# design.net
KiCad netlist of a schematic drawn in Altium Designer
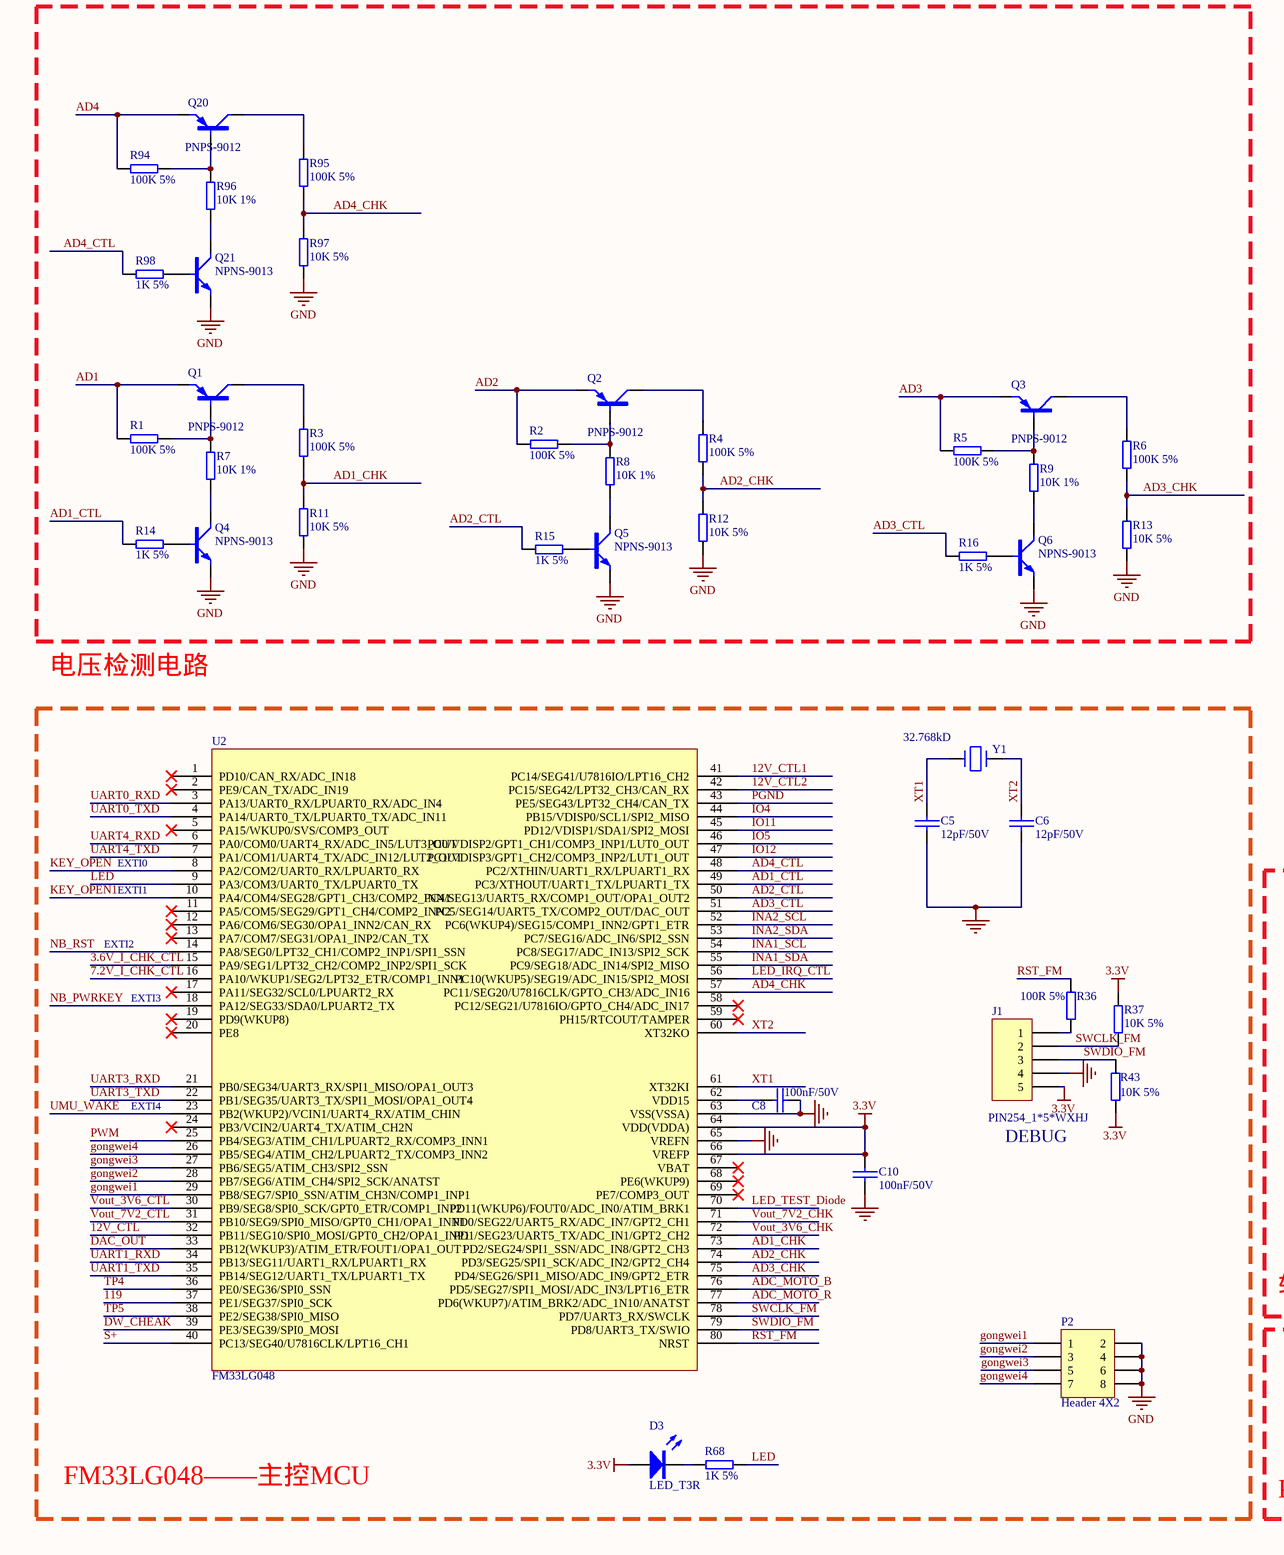
[diagram p0: 主控.SchDoc, left]
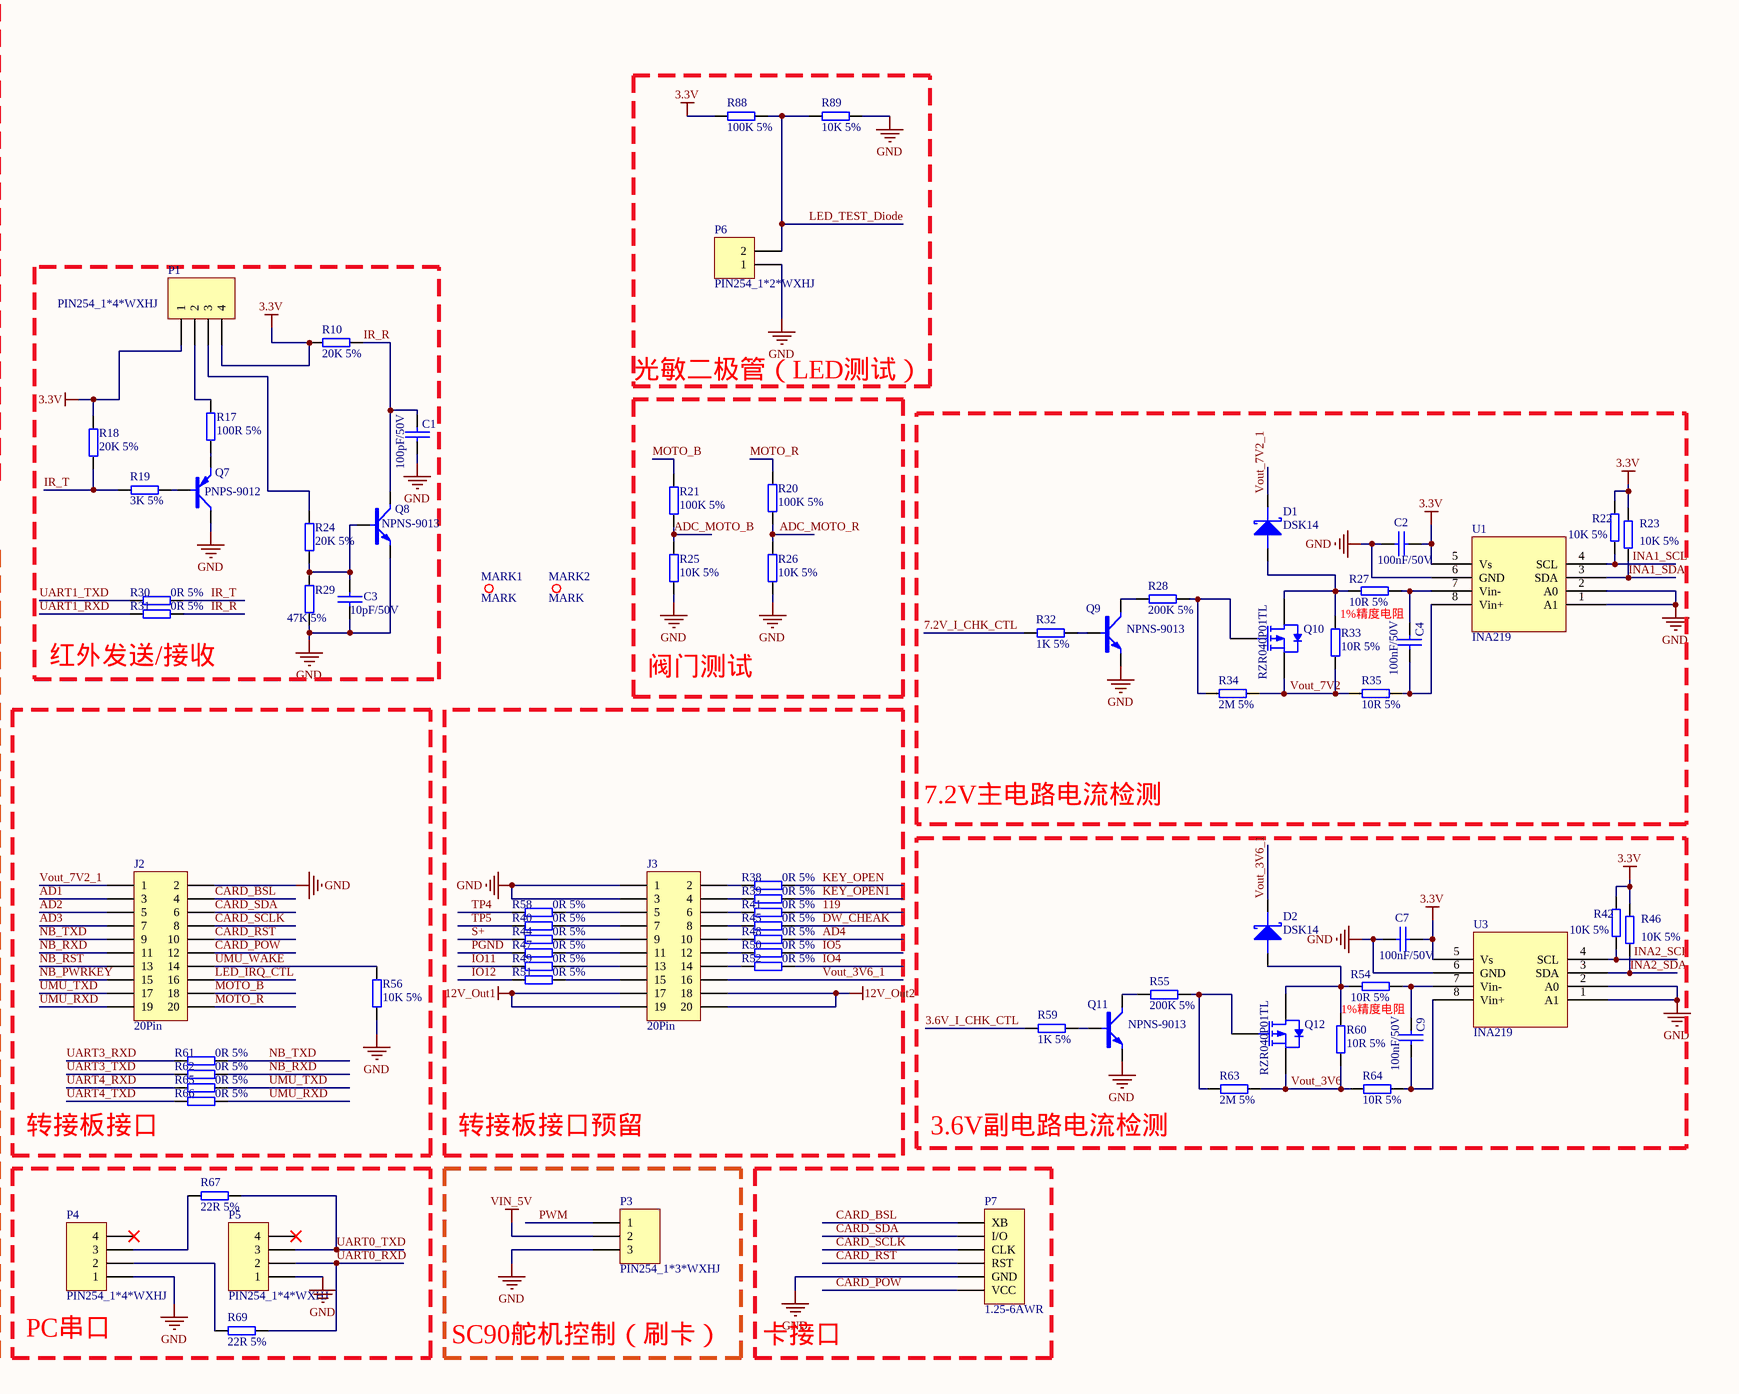
[diagram p1: 主控.SchDoc, right]

(export (version "E")
  (design (tool "Eeschema 10.0.6"))
  (components
    (comp (ref "C1")
      (value "100pF/50V")
      (footprint "CAP0603")
      (description "101pf,50 V,±5%,0603,国巨,CC0603JRNP09BN101")
      (fields (field (name "PART NUMBER") "101020103-0010"))
      (libsource (lib "Database_Libs2") (part "CC03JPO9_101P"))
    )
    (comp (ref "C2")
      (value "100nF/50V")
      (footprint "CAP0603")
      (description "104pF,50 V,±10%,0603,国巨,CC0603KRX7R9BB104")
      (fields (field (name "PART NUMBER") "101020103-0021"))
      (libsource (lib "Database_Libs2") (part "CC03K7R9_100N"))
    )
    (comp (ref "C3")
      (value "10pF/50V")
      (footprint "CAP0603")
      (description "10pF,50 V,±5%,0603,X7R,国巨,CC0603JRNPO9BN100")
      (fields (field (name "PART NUMBER") "101020103-0014"))
      (libsource (lib "Database_Libs2") (part "CC03JPO9_10P"))
    )
    (comp (ref "C4")
      (value "100nF/50V")
      (footprint "CAP0603")
      (description "104pF,50 V,±10%,0603,国巨,CC0603KRX7R9BB104")
      (fields (field (name "PART NUMBER") "101020103-0021"))
      (libsource (lib "Database_Libs2") (part "CC03K7R9_100N"))
    )
    (comp (ref "C5")
      (value "12pF/50V")
      (footprint "CAP0603")
      (description "12P,50 V,±5%,0603,国巨,CC0603JRNPO9BN12")
      (fields (field (name "PART NUMBER") "101020103-0005"))
      (libsource (lib "Database_Libs2") (part "CC03JPO9_12P"))
    )
    (comp (ref "C6")
      (value "12pF/50V")
      (footprint "CAP0603")
      (description "12P,50 V,±5%,0603,国巨,CC0603JRNPO9BN12")
      (fields (field (name "PART NUMBER") "101020103-0005"))
      (libsource (lib "Database_Libs2") (part "CC03JPO9_12P"))
    )
    (comp (ref "C7")
      (value "100nF/50V")
      (footprint "CAP0603")
      (description "104pF,50 V,±10%,0603,国巨,CC0603KRX7R9BB104")
      (fields (field (name "PART NUMBER") "101020103-0021"))
      (libsource (lib "Database_Libs2") (part "CC03K7R9_100N"))
    )
    (comp (ref "C8")
      (value "100nF/50V")
      (footprint "CAP0603")
      (description "104pF,50 V,±10%,0603,国巨,CC0603KRX7R9BB104")
      (fields (field (name "PART NUMBER") "101020103-0021"))
      (libsource (lib "Database_Libs2") (part "CC03K7R9_100N"))
    )
    (comp (ref "C9")
      (value "100nF/50V")
      (footprint "CAP0603")
      (description "104pF,50 V,±10%,0603,国巨,CC0603KRX7R9BB104")
      (fields (field (name "PART NUMBER") "101020103-0021"))
      (libsource (lib "Database_Libs2") (part "CC03K7R9_100N"))
    )
    (comp (ref "C10")
      (value "100nF/50V")
      (footprint "CAP0603")
      (description "104pF,50 V,±10%,0603,国巨,CC0603KRX7R9BB104")
      (fields (field (name "PART NUMBER") "101020103-0021"))
      (libsource (lib "Database_Libs2") (part "CC03K7R9_100N"))
    )
    (comp (ref "D1")
      (value "DSK14")
      (footprint "SOD-123FL")
      (description "DSK14,SOD-123FL,1 A,40 V,28 V,台湾强茂集团苏州群鑫电子,DSK14")
      (fields (field (name "PART NUMBER") "101040101-0043"))
      (libsource (lib "Database_Libs2") (part "02_DSK14"))
    )
    (comp (ref "D2")
      (value "DSK14")
      (footprint "SOD-123FL")
      (description "DSK14,SOD-123FL,1 A,40 V,28 V,台湾强茂集团苏州群鑫电子,DSK14")
      (fields (field (name "PART NUMBER") "101040101-0043"))
      (libsource (lib "Database_Libs2") (part "02_DSK14"))
    )
    (comp (ref "D3")
      (value "LED_T3R")
      (footprint "LED2_300")
      (description "圆形插件,3mm 圆形,插件,红光,湖北匡通电子有限公司,3BB4HC")
      (fields (field (name "PART NUMBER") "101040102-0001"))
      (libsource (lib "Database_Libs2") (part "01-LED_T3R"))
    )
    (comp (ref "J1")
      (value "PIN254_1*5*WXHJ")
      (footprint "PIN254_1*5*1100S")
      (description "1*5 ，Φ1.0 ，2.54mm，直脚,无需焊接器件")
      (fields (field (name "PART NUMBER") "AD_WXHJ_PinHeader_02"))
      (libsource (lib "Database_Libs2") (part "PIN254_1*5*1100S"))
    )
    (comp (ref "J2")
      (value "20Pin")
      (footprint "DC254_2*10 - duplicate")
      (description "DC2 2.54mm 2x10pin,2.54mm间距，2x10pin，32×8.55×27.5mm,母头,双排,双排牛角座")
      (fields (field (name "PART NUMBER") "1010902-0139"))
      (libsource (lib "转接板封装") (part "20Pin"))
    )
    (comp (ref "J3")
      (value "20Pin")
      (footprint "DC254_2*10 - duplicate")
      (description "DC2 2.54mm 2x10pin,2.54mm间距，2x10pin，32×8.55×27.5mm,母头,双排,双排牛角座")
      (fields (field (name "PART NUMBER") "1010902-0139"))
      (libsource (lib "转接板封装") (part "20Pin"))
    )
    (comp (ref "MARK1")
      (value "MARK")
      (footprint "MARK")
      (description "MARK点")
      (fields (field (name "PART NUMBER") "AD_WXHJ_MARK_01"))
      (libsource (lib "转接板封装") (part "MARK"))
    )
    (comp (ref "MARK2")
      (value "MARK")
      (footprint "MARK")
      (description "MARK点")
      (fields (field (name "PART NUMBER") "AD_WXHJ_MARK_01"))
      (libsource (lib "转接板封装") (part "MARK"))
    )
    (comp (ref "P1")
      (value "PIN254_1*4*WXHJ")
      (footprint "PIN254_1*4*1100S")
      (description "1*4 ，Φ1.0 ，2.54mm，直脚,无需焊接器件")
      (fields (field (name "PART NUMBER") "AD_WXHJ_PinHeader_01"))
      (libsource (lib "Database_Libs2") (part "PIN254_1*4*1100S"))
    )
    (comp (ref "P2")
      (value "Header 4X2")
      (footprint "HDR2X4")
      (description "Header, 4-Pin, Dual row")
      (libsource (lib "CBB_Lib_SCH") (part "Header 4X2"))
    )
    (comp (ref "P3")
      (value "PIN254_1*3*WXHJ")
      (footprint "PIN254_1*3*1100S")
      (description "1*3 ，Φ1.0 ，2.54mm，直脚,无需焊接器件")
      (fields (field (name "PART NUMBER") "AD_WXHJ_PinHeader_01"))
      (libsource (lib "模拟计量") (part "PIN254_1*3*1100S"))
    )
    (comp (ref "P4")
      (value "PIN254_1*4*WXHJ")
      (footprint "PIN254_1*4*1100S")
      (description "1*4 ，Φ1.0 ，2.54mm，直脚,无需焊接器件")
      (fields (field (name "PART NUMBER") "AD_WXHJ_PinHeader_01"))
      (libsource (lib "") (part "PIN254_1*4*1100S_1"))
    )
    (comp (ref "P5")
      (value "PIN254_1*4*WXHJ")
      (footprint "PIN254_1*4*1100S")
      (description "1*4 ，Φ1.0 ，2.54mm，直脚,无需焊接器件")
      (fields (field (name "PART NUMBER") "AD_WXHJ_PinHeader_01"))
      (libsource (lib "") (part "PIN254_1*4*1100S_1"))
    )
    (comp (ref "P6")
      (value "PIN254_1*2*WXHJ")
      (footprint "PIN254_1*2*1100S")
      (description "1*2 ，Φ1.0 ，2.54mm，直脚,无需焊接器件")
      (fields (field (name "PART NUMBER") "AD_WXHJ_PinHeader_01"))
      (libsource (lib "转接板封装") (part "PIN254_1*2*1100S"))
    )
    (comp (ref "P7")
      (value "1.25-6AWR")
      (footprint "SMT-1.25-6")
      (description "1.25-6AWR 卷,6针1.25mm,母头,单排,贴片卧式")
      (fields (field (name "PART NUMBER") "1010902-0121"))
      (libsource (lib "Database_Libs2") (part "CARD1608"))
    )
    (comp (ref "Q1")
      (value "PNPS-9012")
      (footprint "SOT-23")
      (description "9012,PNP,SOT-23,JCET;长电,S9012")
      (fields (field (name "PART NUMBER") "101040201-0001"))
      (libsource (lib "Database_Libs2") (part "03_PNPS-9012"))
    )
    (comp (ref "Q2")
      (value "PNPS-9012")
      (footprint "SOT-23")
      (description "9012,PNP,SOT-23,JCET;长电,S9012")
      (fields (field (name "PART NUMBER") "101040201-0001"))
      (libsource (lib "Database_Libs2") (part "03_PNPS-9012"))
    )
    (comp (ref "Q3")
      (value "PNPS-9012")
      (footprint "SOT-23")
      (description "9012,PNP,SOT-23,JCET;长电,S9012")
      (fields (field (name "PART NUMBER") "101040201-0001"))
      (libsource (lib "Database_Libs2") (part "03_PNPS-9012"))
    )
    (comp (ref "Q4")
      (value "NPNS-9013")
      (footprint "SOT-23")
      (description "9013,NPN,SOT-23,长电,S9013")
      (fields (field (name "PART NUMBER") "101040201-0002"))
      (libsource (lib "Database_Libs2") (part "03_NPNS-9013"))
    )
    (comp (ref "Q5")
      (value "NPNS-9013")
      (footprint "SOT-23")
      (description "9013,NPN,SOT-23,长电,S9013")
      (fields (field (name "PART NUMBER") "101040201-0002"))
      (libsource (lib "Database_Libs2") (part "03_NPNS-9013"))
    )
    (comp (ref "Q6")
      (value "NPNS-9013")
      (footprint "SOT-23")
      (description "9013,NPN,SOT-23,长电,S9013")
      (fields (field (name "PART NUMBER") "101040201-0002"))
      (libsource (lib "Database_Libs2") (part "03_NPNS-9013"))
    )
    (comp (ref "Q7")
      (value "PNPS-9012")
      (footprint "SOT-23")
      (description "9012,PNP,SOT-23,JCET;长电,S9012")
      (fields (field (name "PART NUMBER") "101040201-0001"))
      (libsource (lib "Database_Libs2") (part "03_PNPS-9012"))
    )
    (comp (ref "Q8")
      (value "NPNS-9013")
      (footprint "SOT-23")
      (description "9013,NPN,SOT-23,长电,S9013")
      (fields (field (name "PART NUMBER") "101040201-0002"))
      (libsource (lib "Database_Libs2") (part "03_NPNS-9013"))
    )
    (comp (ref "Q9")
      (value "NPNS-9013")
      (footprint "SOT-23")
      (description "9013,NPN,SOT-23,长电,S9013")
      (fields (field (name "PART NUMBER") "101040201-0002"))
      (libsource (lib "Database_Libs2") (part "03_NPNS-9013"))
    )
    (comp (ref "Q10")
      (value "RZR040P01TL")
      (footprint "SOT-23")
      (description "RZR040P01TL；1.5v导通,P-MOS,SOT-23,罗姆,RZR040P01TL")
      (fields (field (name "PART NUMBER") "101040201-0010"))
      (libsource (lib "Database_Libs2") (part "03_P-RZR040P01TL"))
    )
    (comp (ref "Q11")
      (value "NPNS-9013")
      (footprint "SOT-23")
      (description "9013,NPN,SOT-23,长电,S9013")
      (fields (field (name "PART NUMBER") "101040201-0002"))
      (libsource (lib "Database_Libs2") (part "03_NPNS-9013"))
    )
    (comp (ref "Q12")
      (value "RZR040P01TL")
      (footprint "SOT-23")
      (description "RZR040P01TL；1.5v导通,P-MOS,SOT-23,罗姆,RZR040P01TL")
      (fields (field (name "PART NUMBER") "101040201-0010"))
      (libsource (lib "Database_Libs2") (part "03_P-RZR040P01TL"))
    )
    (comp (ref "Q20")
      (value "PNPS-9012")
      (footprint "SOT-23")
      (description "9012,PNP,SOT-23,JCET;长电,S9012")
      (fields (field (name "PART NUMBER") "101040201-0001"))
      (libsource (lib "Database_Libs2") (part "03_PNPS-9012"))
    )
    (comp (ref "Q21")
      (value "NPNS-9013")
      (footprint "SOT-23")
      (description "9013,NPN,SOT-23,长电,S9013")
      (fields (field (name "PART NUMBER") "101040201-0002"))
      (libsource (lib "Database_Libs2") (part "03_NPNS-9013"))
    )
    (comp (ref "R1")
      (value "100K 5%")
      (footprint "RES0603")
      (description "国巨,±5%,0603,,155 ℃,-55 ℃,RC0603JR-07100KL,无铅,100 ppm/℃,1/10W,,100K")
      (fields (field (name "PART NUMBER") "101010103-0005"))
      (libsource (lib "Database_Libs2") (part "RC03J_100K"))
    )
    (comp (ref "R2")
      (value "100K 5%")
      (footprint "RES0603")
      (description "国巨,±5%,0603,,155 ℃,-55 ℃,RC0603JR-07100KL,无铅,100 ppm/℃,1/10W,,100K")
      (fields (field (name "PART NUMBER") "101010103-0005"))
      (libsource (lib "Database_Libs2") (part "RC03J_100K"))
    )
    (comp (ref "R3")
      (value "100K 5%")
      (footprint "RES0603")
      (description "国巨,±5%,0603,,155 ℃,-55 ℃,RC0603JR-07100KL,无铅,100 ppm/℃,1/10W,,100K")
      (fields (field (name "PART NUMBER") "101010103-0005"))
      (libsource (lib "Database_Libs2") (part "RC03J_100K"))
    )
    (comp (ref "R4")
      (value "100K 5%")
      (footprint "RES0603")
      (description "国巨,±5%,0603,,155 ℃,-55 ℃,RC0603JR-07100KL,无铅,100 ppm/℃,1/10W,,100K")
      (fields (field (name "PART NUMBER") "101010103-0005"))
      (libsource (lib "Database_Libs2") (part "RC03J_100K"))
    )
    (comp (ref "R5")
      (value "100K 5%")
      (footprint "RES0603")
      (description "国巨,±5%,0603,,155 ℃,-55 ℃,RC0603JR-07100KL,无铅,100 ppm/℃,1/10W,,100K")
      (fields (field (name "PART NUMBER") "101010103-0005"))
      (libsource (lib "Database_Libs2") (part "RC03J_100K"))
    )
    (comp (ref "R6")
      (value "100K 5%")
      (footprint "RES0603")
      (description "国巨,±5%,0603,,155 ℃,-55 ℃,RC0603JR-07100KL,无铅,100 ppm/℃,1/10W,,100K")
      (fields (field (name "PART NUMBER") "101010103-0005"))
      (libsource (lib "Database_Libs2") (part "RC03J_100K"))
    )
    (comp (ref "R7")
      (value "10K 1%")
      (footprint "RES0603")
      (description "10K±1%,1/10W,0603")
      (fields (field (name "PART NUMBER") "101010103-0052"))
      (libsource (lib "Database_Libs2") (part "RC03J_10K"))
    )
    (comp (ref "R8")
      (value "10K 1%")
      (footprint "RES0603")
      (description "10K±1%,1/10W,0603")
      (fields (field (name "PART NUMBER") "101010103-0052"))
      (libsource (lib "Database_Libs2") (part "RC03J_10K"))
    )
    (comp (ref "R9")
      (value "10K 1%")
      (footprint "RES0603")
      (description "10K±1%,1/10W,0603")
      (fields (field (name "PART NUMBER") "101010103-0052"))
      (libsource (lib "Database_Libs2") (part "RC03J_10K"))
    )
    (comp (ref "R10")
      (value "20K 5%")
      (footprint "RES0603")
      (description "国巨,±5%,0603,,155 ℃,-55 ℃,RC0603JR-0720KL,无铅,200 ppm/℃,1/10W,,20K")
      (fields (field (name "PART NUMBER") "101010103-0004"))
      (libsource (lib "Database_Libs2") (part "RC03J_20K"))
    )
    (comp (ref "R11")
      (value "10K 5%")
      (footprint "RES0603")
      (description "国巨,±5%,0603,,155 ℃,-55 ℃,RC0603JR-0710KL,无铅,200 ppm/℃,1/10W,,10K")
      (fields (field (name "PART NUMBER") "101010103-0003"))
      (libsource (lib "Database_Libs2") (part "RC03J_10K"))
    )
    (comp (ref "R12")
      (value "10K 5%")
      (footprint "RES0603")
      (description "国巨,±5%,0603,,155 ℃,-55 ℃,RC0603JR-0710KL,无铅,200 ppm/℃,1/10W,,10K")
      (fields (field (name "PART NUMBER") "101010103-0003"))
      (libsource (lib "Database_Libs2") (part "RC03J_10K"))
    )
    (comp (ref "R13")
      (value "10K 5%")
      (footprint "RES0603")
      (description "国巨,±5%,0603,,155 ℃,-55 ℃,RC0603JR-0710KL,无铅,200 ppm/℃,1/10W,,10K")
      (fields (field (name "PART NUMBER") "101010103-0003"))
      (libsource (lib "Database_Libs2") (part "RC03J_10K"))
    )
    (comp (ref "R14")
      (value "1K 5%")
      (footprint "RES0603")
      (description "1K,±5%,1/10W,0603,国巨,RC0603JR-071KL")
      (fields (field (name "PART NUMBER") "101010103-0008"))
      (libsource (lib "Database_Libs2") (part "RC03J_1K"))
    )
    (comp (ref "R15")
      (value "1K 5%")
      (footprint "RES0603")
      (description "1K,±5%,1/10W,0603,国巨,RC0603JR-071KL")
      (fields (field (name "PART NUMBER") "101010103-0008"))
      (libsource (lib "Database_Libs2") (part "RC03J_1K"))
    )
    (comp (ref "R16")
      (value "1K 5%")
      (footprint "RES0603")
      (description "1K,±5%,1/10W,0603,国巨,RC0603JR-071KL")
      (fields (field (name "PART NUMBER") "101010103-0008"))
      (libsource (lib "Database_Libs2") (part "RC03J_1K"))
    )
    (comp (ref "R17")
      (value "100R 5%")
      (footprint "RES0603")
      (description "100R,±5%,1/10W,0603,国巨,RC0603JR-07100RL")
      (fields (field (name "PART NUMBER") "101010103-0022"))
      (libsource (lib "Database_Libs2") (part "RC03J_100R"))
    )
    (comp (ref "R18")
      (value "20K 5%")
      (footprint "RES0603")
      (description "国巨,±5%,0603,,155 ℃,-55 ℃,RC0603JR-0720KL,无铅,200 ppm/℃,1/10W,,20K")
      (fields (field (name "PART NUMBER") "101010103-0004"))
      (libsource (lib "Database_Libs2") (part "RC03J_20K"))
    )
    (comp (ref "R19")
      (value "3K 5%")
      (footprint "RES0603")
      (description "国巨,±5%,0603,,155 ℃,-55 ℃,RC0603JR-073KL,无铅,100 ppm/℃,1/10W,,3K")
      (fields (field (name "PART NUMBER") "101010103-0006"))
      (libsource (lib "Database_Libs2") (part "RC03J_3K"))
    )
    (comp (ref "R20")
      (value "100K 5%")
      (footprint "RES0603")
      (description "100K±5%,1/10W,0603")
      (fields (field (name "PART NUMBER") "101010103-0005"))
      (libsource (lib "Database_Libs1") (part "RC03JF_100K"))
    )
    (comp (ref "R21")
      (value "100K 5%")
      (footprint "RES0603")
      (description "100K±5%,1/10W,0603")
      (fields (field (name "PART NUMBER") "101010103-0005"))
      (libsource (lib "Database_Libs1") (part "RC03JF_100K"))
    )
    (comp (ref "R22")
      (value "10K 5%")
      (footprint "RES0603")
      (description "国巨,±5%,0603,,155 ℃,-55 ℃,RC0603JR-0710KL,无铅,200 ppm/℃,1/10W,,10K")
      (fields (field (name "PART NUMBER") "101010103-0003"))
      (libsource (lib "Database_Libs2") (part "RC03J_10K"))
    )
    (comp (ref "R23")
      (value "10K 5%")
      (footprint "RES0603")
      (description "国巨,±5%,0603,,155 ℃,-55 ℃,RC0603JR-0710KL,无铅,200 ppm/℃,1/10W,,10K")
      (fields (field (name "PART NUMBER") "101010103-0003"))
      (libsource (lib "Database_Libs2") (part "RC03J_10K"))
    )
    (comp (ref "R24")
      (value "20K 5%")
      (footprint "RES0603")
      (description "国巨,±5%,0603,,155 ℃,-55 ℃,RC0603JR-0720KL,无铅,200 ppm/℃,1/10W,,20K")
      (fields (field (name "PART NUMBER") "101010103-0004"))
      (libsource (lib "Database_Libs2") (part "RC03J_20K"))
    )
    (comp (ref "R25")
      (value "10K 5%")
      (footprint "RES0603")
      (description "国巨,±5%,0603,,155 ℃,-55 ℃,RC0603JR-0710KL,无铅,200 ppm/℃,1/10W,,10K")
      (fields (field (name "PART NUMBER") "101010103-0003"))
      (libsource (lib "Database_Libs2") (part "RC03J_10K"))
    )
    (comp (ref "R26")
      (value "10K 5%")
      (footprint "RES0603")
      (description "国巨,±5%,0603,,155 ℃,-55 ℃,RC0603JR-0710KL,无铅,200 ppm/℃,1/10W,,10K")
      (fields (field (name "PART NUMBER") "101010103-0003"))
      (libsource (lib "Database_Libs2") (part "RC03J_10K"))
    )
    (comp (ref "R27")
      (value "10R 5%")
      (footprint "RES0603")
      (description "10R,±5%,1/10W,0603,国巨,RC0603JR-0710RL")
      (fields (field (name "PART NUMBER") "101010103-0017"))
      (libsource (lib "Database_Libs2") (part "RC03J_10R"))
    )
    (comp (ref "R28")
      (value "200K 5%")
      (footprint "RES0603")
      (description "200K,±5%,1/10W,0603,国巨,RC0603JR-07200KL")
      (fields (field (name "PART NUMBER") "101010103-0034"))
      (libsource (lib "Database_Libs2") (part "RC03J_200K"))
    )
    (comp (ref "R29")
      (value "47K 5%")
      (footprint "RES0603")
      (description "47K,±5%,1/10W,0603,国巨,RC0603JR-0747KL")
      (fields (field (name "PART NUMBER") "101010103-0012"))
      (libsource (lib "Database_Libs2") (part "RC03J_47K"))
    )
    (comp (ref "R30")
      (value "0R 5%")
      (footprint "RES0603")
      (description "国巨,±5%,0603,,155 ℃,-55 ℃,RC0603J2-070RL,无铅,200 ppm/℃,1/10W,,0R")
      (fields (field (name "PART NUMBER") "101010103-0001"))
      (libsource (lib "Database_Libs2") (part "RC03J_0R"))
    )
    (comp (ref "R31")
      (value "0R 5%")
      (footprint "RES0603")
      (description "国巨,±5%,0603,,155 ℃,-55 ℃,RC0603J2-070RL,无铅,200 ppm/℃,1/10W,,0R")
      (fields (field (name "PART NUMBER") "101010103-0001"))
      (libsource (lib "Database_Libs2") (part "RC03J_0R"))
    )
    (comp (ref "R32")
      (value "1K 5%")
      (footprint "RES0603")
      (description "1K,±5%,1/10W,0603,国巨,RC0603JR-071KL")
      (fields (field (name "PART NUMBER") "101010103-0008"))
      (libsource (lib "Database_Libs2") (part "RC03J_1K"))
    )
    (comp (ref "R33")
      (value "10R 5%")
      (footprint "RES0603")
      (description "10R,±5%,1/10W,0603,国巨,RC0603JR-0710RL")
      (fields (field (name "PART NUMBER") "101010103-0017"))
      (libsource (lib "Database_Libs2") (part "RC03J_10R"))
    )
    (comp (ref "R34")
      (value "2M 5%")
      (footprint "RES0603")
      (description "国巨,±5%,0603,,155 ℃,-55 ℃,RC0603JR-072ML,含铅,100 ppm/℃,1/10W,,2M")
      (fields (field (name "PART NUMBER") "101010103-0025"))
      (libsource (lib "Database_Libs2") (part "RC03J_2M"))
    )
    (comp (ref "R35")
      (value "10R 5%")
      (footprint "RES0603")
      (description "10R,±5%,1/10W,0603,国巨,RC0603JR-0710RL")
      (fields (field (name "PART NUMBER") "101010103-0017"))
      (libsource (lib "Database_Libs2") (part "RC03J_10R"))
    )
    (comp (ref "R36")
      (value "100R 5%")
      (footprint "RES0603")
      (description "100R,±5%,1/10W,0603,国巨,RC0603JR-07100RL")
      (fields (field (name "PART NUMBER") "101010103-0022"))
      (libsource (lib "Database_Libs2") (part "RC03J_100R"))
    )
    (comp (ref "R37")
      (value "10K 5%")
      (footprint "RES0603")
      (description "国巨,±5%,0603,,155 ℃,-55 ℃,RC0603JR-0710KL,无铅,200 ppm/℃,1/10W,,10K")
      (fields (field (name "PART NUMBER") "101010103-0003"))
      (libsource (lib "Database_Libs2") (part "RC03J_10K"))
    )
    (comp (ref "R38")
      (value "0R 5%")
      (footprint "RES0603")
      (description "国巨,±5%,0603,,155 ℃,-55 ℃,RC0603J2-070RL,无铅,200 ppm/℃,1/10W,,0R")
      (fields (field (name "PART NUMBER") "101010103-0001"))
      (libsource (lib "Database_Libs2") (part "RC03J_0R"))
    )
    (comp (ref "R39")
      (value "0R 5%")
      (footprint "RES0603")
      (description "国巨,±5%,0603,,155 ℃,-55 ℃,RC0603J2-070RL,无铅,200 ppm/℃,1/10W,,0R")
      (fields (field (name "PART NUMBER") "101010103-0001"))
      (libsource (lib "Database_Libs2") (part "RC03J_0R"))
    )
    (comp (ref "R40")
      (value "0R 5%")
      (footprint "RES0603")
      (description "国巨,±5%,0603,,155 ℃,-55 ℃,RC0603J2-070RL,无铅,200 ppm/℃,1/10W,,0R")
      (fields (field (name "PART NUMBER") "101010103-0001"))
      (libsource (lib "Database_Libs2") (part "RC03J_0R"))
    )
    (comp (ref "R41")
      (value "0R 5%")
      (footprint "RES0603")
      (description "国巨,±5%,0603,,155 ℃,-55 ℃,RC0603J2-070RL,无铅,200 ppm/℃,1/10W,,0R")
      (fields (field (name "PART NUMBER") "101010103-0001"))
      (libsource (lib "Database_Libs2") (part "RC03J_0R"))
    )
    (comp (ref "R42")
      (value "10K 5%")
      (footprint "RES0603")
      (description "国巨,±5%,0603,,155 ℃,-55 ℃,RC0603JR-0710KL,无铅,200 ppm/℃,1/10W,,10K")
      (fields (field (name "PART NUMBER") "101010103-0003"))
      (libsource (lib "Database_Libs2") (part "RC03J_10K"))
    )
    (comp (ref "R43")
      (value "10K 5%")
      (footprint "RES0603")
      (description "国巨,±5%,0603,,155 ℃,-55 ℃,RC0603JR-0710KL,无铅,200 ppm/℃,1/10W,,10K")
      (fields (field (name "PART NUMBER") "101010103-0003"))
      (libsource (lib "Database_Libs2") (part "RC03J_10K"))
    )
    (comp (ref "R44")
      (value "0R 5%")
      (footprint "RES0603")
      (description "国巨,±5%,0603,,155 ℃,-55 ℃,RC0603J2-070RL,无铅,200 ppm/℃,1/10W,,0R")
      (fields (field (name "PART NUMBER") "101010103-0001"))
      (libsource (lib "Database_Libs2") (part "RC03J_0R"))
    )
    (comp (ref "R45")
      (value "0R 5%")
      (footprint "RES0603")
      (description "国巨,±5%,0603,,155 ℃,-55 ℃,RC0603J2-070RL,无铅,200 ppm/℃,1/10W,,0R")
      (fields (field (name "PART NUMBER") "101010103-0001"))
      (libsource (lib "Database_Libs2") (part "RC03J_0R"))
    )
    (comp (ref "R46")
      (value "10K 5%")
      (footprint "RES0603")
      (description "国巨,±5%,0603,,155 ℃,-55 ℃,RC0603JR-0710KL,无铅,200 ppm/℃,1/10W,,10K")
      (fields (field (name "PART NUMBER") "101010103-0003"))
      (libsource (lib "Database_Libs2") (part "RC03J_10K"))
    )
    (comp (ref "R47")
      (value "0R 5%")
      (footprint "RES0603")
      (description "国巨,±5%,0603,,155 ℃,-55 ℃,RC0603J2-070RL,无铅,200 ppm/℃,1/10W,,0R")
      (fields (field (name "PART NUMBER") "101010103-0001"))
      (libsource (lib "Database_Libs2") (part "RC03J_0R"))
    )
    (comp (ref "R48")
      (value "0R 5%")
      (footprint "RES0603")
      (description "国巨,±5%,0603,,155 ℃,-55 ℃,RC0603J2-070RL,无铅,200 ppm/℃,1/10W,,0R")
      (fields (field (name "PART NUMBER") "101010103-0001"))
      (libsource (lib "Database_Libs2") (part "RC03J_0R"))
    )
    (comp (ref "R49")
      (value "0R 5%")
      (footprint "RES0603")
      (description "国巨,±5%,0603,,155 ℃,-55 ℃,RC0603J2-070RL,无铅,200 ppm/℃,1/10W,,0R")
      (fields (field (name "PART NUMBER") "101010103-0001"))
      (libsource (lib "Database_Libs2") (part "RC03J_0R"))
    )
    (comp (ref "R50")
      (value "0R 5%")
      (footprint "RES0603")
      (description "国巨,±5%,0603,,155 ℃,-55 ℃,RC0603J2-070RL,无铅,200 ppm/℃,1/10W,,0R")
      (fields (field (name "PART NUMBER") "101010103-0001"))
      (libsource (lib "Database_Libs2") (part "RC03J_0R"))
    )
    (comp (ref "R51")
      (value "0R 5%")
      (footprint "RES0603")
      (description "国巨,±5%,0603,,155 ℃,-55 ℃,RC0603J2-070RL,无铅,200 ppm/℃,1/10W,,0R")
      (fields (field (name "PART NUMBER") "101010103-0001"))
      (libsource (lib "Database_Libs2") (part "RC03J_0R"))
    )
    (comp (ref "R52")
      (value "0R 5%")
      (footprint "RES0603")
      (description "国巨,±5%,0603,,155 ℃,-55 ℃,RC0603J2-070RL,无铅,200 ppm/℃,1/10W,,0R")
      (fields (field (name "PART NUMBER") "101010103-0001"))
      (libsource (lib "Database_Libs2") (part "RC03J_0R"))
    )
    (comp (ref "R54")
      (value "10R 5%")
      (footprint "RES0603")
      (description "10R,±5%,1/10W,0603,国巨,RC0603JR-0710RL")
      (fields (field (name "PART NUMBER") "101010103-0017"))
      (libsource (lib "Database_Libs2") (part "RC03J_10R"))
    )
    (comp (ref "R55")
      (value "200K 5%")
      (footprint "RES0603")
      (description "200K,±5%,1/10W,0603,国巨,RC0603JR-07200KL")
      (fields (field (name "PART NUMBER") "101010103-0034"))
      (libsource (lib "Database_Libs2") (part "RC03J_200K"))
    )
    (comp (ref "R56")
      (value "10K 5%")
      (footprint "RES0603")
      (description "国巨,±5%,0603,,155 ℃,-55 ℃,RC0603JR-0710KL,无铅,200 ppm/℃,1/10W,,10K")
      (fields (field (name "PART NUMBER") "101010103-0003"))
      (libsource (lib "Database_Libs2") (part "RC03J_10K"))
    )
    (comp (ref "R58")
      (value "0R 5%")
      (footprint "RES0603")
      (description "国巨,±5%,0603,,155 ℃,-55 ℃,RC0603J2-070RL,无铅,200 ppm/℃,1/10W,,0R")
      (fields (field (name "PART NUMBER") "101010103-0001"))
      (libsource (lib "Database_Libs2") (part "RC03J_0R"))
    )
    (comp (ref "R59")
      (value "1K 5%")
      (footprint "RES0603")
      (description "1K,±5%,1/10W,0603,国巨,RC0603JR-071KL")
      (fields (field (name "PART NUMBER") "101010103-0008"))
      (libsource (lib "Database_Libs2") (part "RC03J_1K"))
    )
    (comp (ref "R60")
      (value "10R 5%")
      (footprint "RES0603")
      (description "10R,±5%,1/10W,0603,国巨,RC0603JR-0710RL")
      (fields (field (name "PART NUMBER") "101010103-0017"))
      (libsource (lib "Database_Libs2") (part "RC03J_10R"))
    )
    (comp (ref "R61")
      (value "0R 5%")
      (footprint "RES0603")
      (description "国巨,±5%,0603,,155 ℃,-55 ℃,RC0603J2-070RL,无铅,200 ppm/℃,1/10W,,0R")
      (fields (field (name "PART NUMBER") "101010103-0001"))
      (libsource (lib "Database_Libs2") (part "RC03J_0R"))
    )
    (comp (ref "R62")
      (value "0R 5%")
      (footprint "RES0603")
      (description "国巨,±5%,0603,,155 ℃,-55 ℃,RC0603J2-070RL,无铅,200 ppm/℃,1/10W,,0R")
      (fields (field (name "PART NUMBER") "101010103-0001"))
      (libsource (lib "Database_Libs2") (part "RC03J_0R"))
    )
    (comp (ref "R63")
      (value "2M 5%")
      (footprint "RES0603")
      (description "国巨,±5%,0603,,155 ℃,-55 ℃,RC0603JR-072ML,含铅,100 ppm/℃,1/10W,,2M")
      (fields (field (name "PART NUMBER") "101010103-0025"))
      (libsource (lib "Database_Libs2") (part "RC03J_2M"))
    )
    (comp (ref "R64")
      (value "10R 5%")
      (footprint "RES0603")
      (description "10R,±5%,1/10W,0603,国巨,RC0603JR-0710RL")
      (fields (field (name "PART NUMBER") "101010103-0017"))
      (libsource (lib "Database_Libs2") (part "RC03J_10R"))
    )
    (comp (ref "R65")
      (value "0R 5%")
      (footprint "RES0603")
      (description "国巨,±5%,0603,,155 ℃,-55 ℃,RC0603J2-070RL,无铅,200 ppm/℃,1/10W,,0R")
      (fields (field (name "PART NUMBER") "101010103-0001"))
      (libsource (lib "Database_Libs2") (part "RC03J_0R"))
    )
    (comp (ref "R66")
      (value "0R 5%")
      (footprint "RES0603")
      (description "国巨,±5%,0603,,155 ℃,-55 ℃,RC0603J2-070RL,无铅,200 ppm/℃,1/10W,,0R")
      (fields (field (name "PART NUMBER") "101010103-0001"))
      (libsource (lib "Database_Libs2") (part "RC03J_0R"))
    )
    (comp (ref "R67")
      (value "22R 5%")
      (footprint "RES0603")
      (description "国巨,±5%,0603,,155 ℃,-55 ℃,RC0603JR-0722RL,无铅,200 ppm/℃,1/10W,,22欧")
      (fields (field (name "PART NUMBER") "101010103-0009"))
      (libsource (lib "Database_Libs2") (part "RC03J_22R"))
    )
    (comp (ref "R68")
      (value "1K 5%")
      (footprint "RES0603")
      (description "1K,±5%,1/10W,0603,国巨,RC0603JR-071KL")
      (fields (field (name "PART NUMBER") "101010103-0008"))
      (libsource (lib "Database_Libs2") (part "RC03J_1K"))
    )
    (comp (ref "R69")
      (value "22R 5%")
      (footprint "RES0603")
      (description "国巨,±5%,0603,,155 ℃,-55 ℃,RC0603JR-0722RL,无铅,200 ppm/℃,1/10W,,22欧")
      (fields (field (name "PART NUMBER") "101010103-0009"))
      (libsource (lib "Database_Libs2") (part "RC03J_22R"))
    )
    (comp (ref "R88")
      (value "100K 5%")
      (footprint "RES0603")
      (description "国巨,±5%,0603,,155 ℃,-55 ℃,RC0603JR-07100KL,无铅,100 ppm/℃,1/10W,,100K")
      (fields (field (name "PART NUMBER") "101010103-0005"))
      (libsource (lib "Database_Libs2") (part "RC03J_100K"))
    )
    (comp (ref "R89")
      (value "10K 5%")
      (footprint "RES0603")
      (description "国巨,±5%,0603,,155 ℃,-55 ℃,RC0603JR-0710KL,无铅,200 ppm/℃,1/10W,,10K")
      (fields (field (name "PART NUMBER") "101010103-0003"))
      (libsource (lib "转接板封装") (part "RC03J_10K"))
    )
    (comp (ref "R94")
      (value "100K 5%")
      (footprint "RES0603")
      (description "国巨,±5%,0603,,155 ℃,-55 ℃,RC0603JR-07100KL,无铅,100 ppm/℃,1/10W,,100K")
      (fields (field (name "PART NUMBER") "101010103-0005"))
      (libsource (lib "Database_Libs2") (part "RC03J_100K"))
    )
    (comp (ref "R95")
      (value "100K 5%")
      (footprint "RES0603")
      (description "国巨,±5%,0603,,155 ℃,-55 ℃,RC0603JR-07100KL,无铅,100 ppm/℃,1/10W,,100K")
      (fields (field (name "PART NUMBER") "101010103-0005"))
      (libsource (lib "Database_Libs2") (part "RC03J_100K"))
    )
    (comp (ref "R96")
      (value "10K 1%")
      (footprint "RES0603")
      (description "10K±1%,1/10W,0603")
      (fields (field (name "PART NUMBER") "101010103-0052"))
      (libsource (lib "Database_Libs2") (part "RC03J_10K"))
    )
    (comp (ref "R97")
      (value "10K 5%")
      (footprint "RES0603")
      (description "国巨,±5%,0603,,155 ℃,-55 ℃,RC0603JR-0710KL,无铅,200 ppm/℃,1/10W,,10K")
      (fields (field (name "PART NUMBER") "101010103-0003"))
      (libsource (lib "Database_Libs2") (part "RC03J_10K"))
    )
    (comp (ref "R98")
      (value "1K 5%")
      (footprint "RES0603")
      (description "1K,±5%,1/10W,0603,国巨,RC0603JR-071KL")
      (fields (field (name "PART NUMBER") "101010103-0008"))
      (libsource (lib "Database_Libs2") (part "RC03J_1K"))
    )
    (comp (ref "U1") (value "INA219") (footprint "SO-8") (libsource (lib "转接板封装") (part "INA219")))
    (comp (ref "U2")
      (value "FM33LG048")
      (footprint "LQFP80")
      (description "101050101-0261")
      (libsource (lib "转接板封装") (part "FM33LG048"))
    )
    (comp (ref "U3") (value "INA219") (footprint "SO-8") (libsource (lib "转接板封装") (part "INA219")))
    (comp (ref "Y1")
      (value "32.768kD")
      (footprint "SMD-3215_2P")
      (fields (field (name "PART NUMBER") "1010601-0020"))
      (libsource (lib "Database_Libs2") (part "04_XTALSG12MD_32.768kD"))
    )
  )
  (nets
    (net (code "1") (name "/3.6V_I_CHK_CTL") (class "Default")
      (node (ref "R59") (pin "2") (pinfunction "2_2") (pintype "passive"))
      (node (ref "U2") (pin "15") (pinfunction "PA9/SEG1/LPT32_CH2/COMP2_INP2/SPI1_SCK_15") (pintype "passive"))
    )
    (net (code "2") (name "/7.2V_I_CHK_CTL") (class "Default")
      (node (ref "R32") (pin "2") (pinfunction "2_2") (pintype "passive"))
      (node (ref "U2") (pin "16") (pinfunction "PA10/WKUP1/SEG2/LPT32_ETR/COMP1_INN1_16") (pintype "passive"))
    )
    (net (code "3") (name "/12V_CTL") (class "Default")
      (node (ref "U2") (pin "32") (pinfunction "PB11/SEG10/SPI0_MOSI/GPT0_CH2/OPA1_INP1_32") (pintype "passive"))
    )
    (net (code "4") (name "/12V_CTL1") (class "Default")
      (node (ref "U2") (pin "41") (pinfunction "PC14/SEG41/U7816IO/LPT16_CH2_41") (pintype "passive"))
    )
    (net (code "5") (name "/12V_CTL2") (class "Default")
      (node (ref "U2") (pin "42") (pinfunction "PC15/SEG42/LPT32_CH3/CAN_RX_42") (pintype "passive"))
    )
    (net (code "6") (name "/119") (class "Default")
      (node (ref "R41") (pin "2") (pinfunction "2_2") (pintype "passive"))
      (node (ref "U2") (pin "37") (pinfunction "PE1/SEG37/SPI0_SCK_37") (pintype "passive"))
    )
    (net (code "7") (name "/AD1") (class "Default")
      (node (ref "J2") (pin "3") (pinfunction "3_3") (pintype "passive"))
      (node (ref "Q1") (pin "2") (pinfunction "E_2") (pintype "passive"))
      (node (ref "R1") (pin "2") (pinfunction "2_2") (pintype "passive"))
    )
    (net (code "8") (name "/AD1_CHK") (class "Default")
      (node (ref "R11") (pin "1") (pinfunction "1_1") (pintype "passive"))
      (node (ref "R3") (pin "2") (pinfunction "2_2") (pintype "passive"))
      (node (ref "U2") (pin "73") (pinfunction "PD2/SEG24/SPI1_SSN/ADC_IN8/GPT2_CH3_73") (pintype "passive"))
    )
    (net (code "9") (name "/AD1_CTL") (class "Default")
      (node (ref "R14") (pin "1") (pinfunction "1_1") (pintype "passive"))
      (node (ref "U2") (pin "49") (pinfunction "PC3/XTHOUT/UART1_TX/LPUART1_TX_49") (pintype "passive"))
    )
    (net (code "10") (name "/AD2") (class "Default")
      (node (ref "J2") (pin "5") (pinfunction "5_5") (pintype "passive"))
      (node (ref "Q2") (pin "2") (pinfunction "E_2") (pintype "passive"))
      (node (ref "R2") (pin "2") (pinfunction "2_2") (pintype "passive"))
    )
    (net (code "11") (name "/AD2_CHK") (class "Default")
      (node (ref "R12") (pin "1") (pinfunction "1_1") (pintype "passive"))
      (node (ref "R4") (pin "2") (pinfunction "2_2") (pintype "passive"))
      (node (ref "U2") (pin "74") (pinfunction "PD3/SEG25/SPI1_SCK/ADC_IN2/GPT2_CH4_74") (pintype "passive"))
    )
    (net (code "12") (name "/AD2_CTL") (class "Default")
      (node (ref "R15") (pin "1") (pinfunction "1_1") (pintype "passive"))
      (node (ref "U2") (pin "50") (pinfunction "PC4/SEG13/UART5_RX/COMP1_OUT/OPA1_OUT2_50") (pintype "passive"))
    )
    (net (code "13") (name "/AD3") (class "Default")
      (node (ref "J2") (pin "7") (pinfunction "7_7") (pintype "passive"))
      (node (ref "Q3") (pin "2") (pinfunction "E_2") (pintype "passive"))
      (node (ref "R5") (pin "2") (pinfunction "2_2") (pintype "passive"))
    )
    (net (code "14") (name "/AD3_CHK") (class "Default")
      (node (ref "R13") (pin "1") (pinfunction "1_1") (pintype "passive"))
      (node (ref "R6") (pin "2") (pinfunction "2_2") (pintype "passive"))
      (node (ref "U2") (pin "75") (pinfunction "PD4/SEG26/SPI1_MISO/ADC_IN9/GPT2_ETR_75") (pintype "passive"))
    )
    (net (code "15") (name "/AD3_CTL") (class "Default")
      (node (ref "R16") (pin "1") (pinfunction "1_1") (pintype "passive"))
      (node (ref "U2") (pin "51") (pinfunction "PC5/SEG14/UART5_TX/COMP2_OUT/DAC_OUT_51") (pintype "passive"))
    )
    (net (code "16") (name "/AD4") (class "Default")
      (node (ref "Q20") (pin "2") (pinfunction "E_2") (pintype "passive"))
      (node (ref "R48") (pin "2") (pinfunction "2_2") (pintype "passive"))
      (node (ref "R94") (pin "2") (pinfunction "2_2") (pintype "passive"))
    )
    (net (code "17") (name "/AD4_CHK") (class "Default")
      (node (ref "R95") (pin "2") (pinfunction "2_2") (pintype "passive"))
      (node (ref "R97") (pin "1") (pinfunction "1_1") (pintype "passive"))
      (node (ref "U2") (pin "57") (pinfunction "PC11/SEG20/U7816CLK/GPTO_CH3/ADC_IN16_57") (pintype "passive"))
    )
    (net (code "18") (name "/AD4_CTL") (class "Default")
      (node (ref "R98") (pin "1") (pinfunction "1_1") (pintype "passive"))
      (node (ref "U2") (pin "48") (pinfunction "PC2/XTHIN/UART1_RX/LPUART1_RX_48") (pintype "passive"))
    )
    (net (code "19") (name "/ADC_MOTO_B") (class "Default")
      (node (ref "R21") (pin "1") (pinfunction "1_1") (pintype "passive"))
      (node (ref "R25") (pin "2") (pinfunction "2_2") (pintype "passive"))
      (node (ref "U2") (pin "76") (pinfunction "PD5/SEG27/SPI1_MOSI/ADC_IN3/LPT16_ETR_76") (pintype "passive"))
    )
    (net (code "20") (name "/ADC_MOTO_R") (class "Default")
      (node (ref "R20") (pin "1") (pinfunction "1_1") (pintype "passive"))
      (node (ref "R26") (pin "2") (pinfunction "2_2") (pintype "passive"))
      (node (ref "U2") (pin "77") (pinfunction "PD6(WKUP7)/ATIM_BRK2/ADC_1N10/ANATST_77") (pintype "passive"))
    )
    (net (code "21") (name "/CARD_BSL") (class "Default")
      (node (ref "J2") (pin "4") (pinfunction "4_4") (pintype "passive"))
      (node (ref "P7") (pin "1") (pinfunction "XB_1") (pintype "passive"))
    )
    (net (code "22") (name "/CARD_POW") (class "Default")
      (node (ref "J2") (pin "12") (pinfunction "12_12") (pintype "passive"))
      (node (ref "P7") (pin "6") (pinfunction "VCC_6") (pintype "passive"))
    )
    (net (code "23") (name "/CARD_RST") (class "Default")
      (node (ref "J2") (pin "10") (pinfunction "10_10") (pintype "passive"))
      (node (ref "P7") (pin "4") (pinfunction "RST_4") (pintype "passive"))
    )
    (net (code "24") (name "/CARD_SCLK") (class "Default")
      (node (ref "J2") (pin "8") (pinfunction "8_8") (pintype "passive"))
      (node (ref "P7") (pin "3") (pinfunction "CLK_3") (pintype "passive"))
    )
    (net (code "25") (name "/CARD_SDA") (class "Default")
      (node (ref "J2") (pin "6") (pinfunction "6_6") (pintype "passive"))
      (node (ref "P7") (pin "2") (pinfunction "I/O_2") (pintype "passive"))
    )
    (net (code "26") (name "/DAC_OUT") (class "Default")
      (node (ref "U2") (pin "33") (pinfunction "PB12(WKUP3)/ATIM_ETR/FOUT1/OPA1_OUT1_33") (pintype "passive"))
    )
    (net (code "27") (name "/DW_CHEAK") (class "Default")
      (node (ref "R45") (pin "2") (pinfunction "2_2") (pintype "passive"))
      (node (ref "U2") (pin "39") (pinfunction "PE3/SEG39/SPI0_MOSI_39") (pintype "passive"))
    )
    (net (code "28") (name "/INA1_SCL") (class "Default")
      (node (ref "R22") (pin "2") (pinfunction "2_2") (pintype "passive"))
      (node (ref "U1") (pin "4") (pinfunction "SCL_4") (pintype "passive"))
      (node (ref "U2") (pin "54") (pinfunction "PC8/SEG17/ADC_IN13/SPI2_SCK_54") (pintype "passive"))
    )
    (net (code "29") (name "/INA1_SDA") (class "Default")
      (node (ref "R23") (pin "2") (pinfunction "2_2") (pintype "passive"))
      (node (ref "U1") (pin "3") (pinfunction "SDA_3") (pintype "passive"))
      (node (ref "U2") (pin "55") (pinfunction "PC9/SEG18/ADC_IN14/SPI2_MISO_55") (pintype "passive"))
    )
    (net (code "30") (name "/INA2_SCL") (class "Default")
      (node (ref "R42") (pin "2") (pinfunction "2_2") (pintype "passive"))
      (node (ref "U2") (pin "52") (pinfunction "PC6(WKUP4)/SEG15/COMP1_INN2/GPT1_ETR_52") (pintype "passive"))
      (node (ref "U3") (pin "4") (pinfunction "SCL_4") (pintype "passive"))
    )
    (net (code "31") (name "/INA2_SDA") (class "Default")
      (node (ref "R46") (pin "2") (pinfunction "2_2") (pintype "passive"))
      (node (ref "U2") (pin "53") (pinfunction "PC7/SEG16/ADC_IN6/SPI2_SSN_53") (pintype "passive"))
      (node (ref "U3") (pin "3") (pinfunction "SDA_3") (pintype "passive"))
    )
    (net (code "32") (name "/IO4") (class "Default")
      (node (ref "R52") (pin "2") (pinfunction "2_2") (pintype "passive"))
      (node (ref "U2") (pin "44") (pinfunction "PB15/VDISP0/SCL1/SPI2_MISO_44") (pintype "passive"))
    )
    (net (code "33") (name "/IO5") (class "Default")
      (node (ref "R50") (pin "2") (pinfunction "2_2") (pintype "passive"))
      (node (ref "U2") (pin "46") (pinfunction "PC0/VDISP2/GPT1_CH1/COMP3_INP1/LUT0_OUT_46") (pintype "passive"))
    )
    (net (code "34") (name "/IO11") (class "Default")
      (node (ref "R49") (pin "1") (pinfunction "1_1") (pintype "passive"))
      (node (ref "U2") (pin "45") (pinfunction "PD12/VDISP1/SDA1/SPI2_MOSI_45") (pintype "passive"))
    )
    (net (code "35") (name "/IO12") (class "Default")
      (node (ref "R51") (pin "1") (pinfunction "1_1") (pintype "passive"))
      (node (ref "U2") (pin "47") (pinfunction "PC1/VDISP3/GPT1_CH2/COMP3_INP2/LUT1_OUT_47") (pintype "passive"))
    )
    (net (code "36") (name "/IR_R") (class "Default")
      (node (ref "C1") (pin "1") (pinfunction "1_1") (pintype "passive"))
      (node (ref "Q8") (pin "3") (pinfunction "C_3") (pintype "passive"))
      (node (ref "R10") (pin "2") (pinfunction "2_2") (pintype "passive"))
      (node (ref "R31") (pin "2") (pinfunction "2_2") (pintype "passive"))
    )
    (net (code "37") (name "/IR_T") (class "Default")
      (node (ref "R18") (pin "1") (pinfunction "1_1") (pintype "passive"))
      (node (ref "R19") (pin "1") (pinfunction "1_1") (pintype "passive"))
      (node (ref "R30") (pin "2") (pinfunction "2_2") (pintype "passive"))
    )
    (net (code "38") (name "/KEY_OPEN") (class "Default")
      (node (ref "R38") (pin "2") (pinfunction "2_2") (pintype "passive"))
      (node (ref "U2") (pin "8") (pinfunction "PA2/COM2/UART0_RX/LPUART0_RX_8") (pintype "passive"))
    )
    (net (code "39") (name "/KEY_OPEN1") (class "Default")
      (node (ref "R39") (pin "2") (pinfunction "2_2") (pintype "passive"))
      (node (ref "U2") (pin "10") (pinfunction "PA4/COM4/SEG28/GPT1_CH3/COMP2_INN1_10") (pintype "passive"))
    )
    (net (code "40") (name "/LED") (class "Default")
      (node (ref "R68") (pin "1") (pinfunction "1_1") (pintype "passive"))
      (node (ref "U2") (pin "9") (pinfunction "PA3/COM3/UART0_TX/LPUART0_TX_9") (pintype "passive"))
    )
    (net (code "41") (name "/LED_IRQ_CTL") (class "Default")
      (node (ref "J2") (pin "16") (pinfunction "16_16") (pintype "passive"))
      (node (ref "U2") (pin "56") (pinfunction "PC10(WKUP5)/SEG19/ADC_IN15/SPI2_MOSI_56") (pintype "passive"))
    )
    (net (code "42") (name "/LED_TEST_Diode") (class "Default")
      (node (ref "P6") (pin "2") (pinfunction "2_2") (pintype "passive"))
      (node (ref "R88") (pin "2") (pinfunction "2_2") (pintype "passive"))
      (node (ref "R89") (pin "2") (pinfunction "2_2") (pintype "passive"))
      (node (ref "U2") (pin "70") (pinfunction "PD11(WKUP6)/FOUT0/ADC_IN0/ATIM_BRK1_70") (pintype "passive"))
    )
    (net (code "43") (name "/MOTO_B") (class "Default")
      (node (ref "J2") (pin "18") (pinfunction "18_18") (pintype "passive"))
      (node (ref "R21") (pin "2") (pinfunction "2_2") (pintype "passive"))
    )
    (net (code "44") (name "/MOTO_R") (class "Default")
      (node (ref "J2") (pin "20") (pinfunction "20_20") (pintype "passive"))
      (node (ref "R20") (pin "2") (pinfunction "2_2") (pintype "passive"))
    )
    (net (code "45") (name "/NB_PWRKEY") (class "Default")
      (node (ref "J2") (pin "15") (pinfunction "15_15") (pintype "passive"))
      (node (ref "U2") (pin "18") (pinfunction "PA12/SEG33/SDA0/LPUART2_TX_18") (pintype "passive"))
    )
    (net (code "46") (name "/NB_RST") (class "Default")
      (node (ref "J2") (pin "13") (pinfunction "13_13") (pintype "passive"))
      (node (ref "U2") (pin "14") (pinfunction "PA8/SEG0/LPT32_CH1/COMP2_INP1/SPI1_SSN_14") (pintype "passive"))
    )
    (net (code "47") (name "/NB_RXD") (class "Default")
      (node (ref "J2") (pin "11") (pinfunction "11_11") (pintype "passive"))
      (node (ref "R62") (pin "2") (pinfunction "2_2") (pintype "passive"))
    )
    (net (code "48") (name "/NB_TXD") (class "Default")
      (node (ref "J2") (pin "9") (pinfunction "9_9") (pintype "passive"))
      (node (ref "R61") (pin "2") (pinfunction "2_2") (pintype "passive"))
    )
    (net (code "49") (name "/PGND") (class "Default")
      (node (ref "R47") (pin "1") (pinfunction "1_1") (pintype "passive"))
      (node (ref "U2") (pin "43") (pinfunction "PE5/SEG43/LPT32_CH4/CAN_TX_43") (pintype "passive"))
    )
    (net (code "50") (name "/PWM") (class "Default")
      (node (ref "P3") (pin "1") (pinfunction "1_1") (pintype "passive"))
      (node (ref "U2") (pin "25") (pinfunction "PB4/SEG3/ATIM_CH1/LPUART2_RX/COMP3_INN1_25") (pintype "passive"))
    )
    (net (code "51") (name "/RST_FM") (class "Default")
      (node (ref "R36") (pin "1") (pinfunction "1_1") (pintype "passive"))
      (node (ref "U2") (pin "80") (pinfunction "NRST_80") (pintype "passive"))
    )
    (net (code "52") (name "/S+") (class "Default")
      (node (ref "R44") (pin "1") (pinfunction "1_1") (pintype "passive"))
      (node (ref "U2") (pin "40") (pinfunction "PC13/SEG40/U7816CLK/LPT16_CH1_40") (pintype "passive"))
    )
    (net (code "53") (name "/SWCLK_FM") (class "Default")
      (node (ref "J1") (pin "2") (pinfunction "2_2") (pintype "passive"))
      (node (ref "R37") (pin "2") (pinfunction "2_2") (pintype "passive"))
      (node (ref "U2") (pin "78") (pinfunction "PD7/UART3_RX/SWCLK_78") (pintype "passive"))
    )
    (net (code "54") (name "/SWDIO_FM") (class "Default")
      (node (ref "J1") (pin "3") (pinfunction "3_3") (pintype "passive"))
      (node (ref "R43") (pin "2") (pinfunction "2_2") (pintype "passive"))
      (node (ref "U2") (pin "79") (pinfunction "PD8/UART3_TX/SWIO_79") (pintype "passive"))
    )
    (net (code "55") (name "/TP4") (class "Default")
      (node (ref "R58") (pin "1") (pinfunction "1_1") (pintype "passive"))
      (node (ref "U2") (pin "36") (pinfunction "PE0/SEG36/SPI0_SSN_36") (pintype "passive"))
    )
    (net (code "56") (name "/TP5") (class "Default")
      (node (ref "R40") (pin "1") (pinfunction "1_1") (pintype "passive"))
      (node (ref "U2") (pin "38") (pinfunction "PE2/SEG38/SPI0_MISO_38") (pintype "passive"))
    )
    (net (code "57") (name "/UART0_RXD") (class "Default")
      (node (ref "P5") (pin "2") (pinfunction "2_2") (pintype "passive"))
      (node (ref "R69") (pin "2") (pinfunction "2_2") (pintype "passive"))
      (node (ref "U2") (pin "3") (pinfunction "PA13/UART0_RX/LPUART0_RX/ADC_IN4_3") (pintype "passive"))
    )
    (net (code "58") (name "/UART0_TXD") (class "Default")
      (node (ref "P5") (pin "3") (pinfunction "3_3") (pintype "passive"))
      (node (ref "R67") (pin "2") (pinfunction "2_2") (pintype "passive"))
      (node (ref "U2") (pin "4") (pinfunction "PA14/UART0_TX/LPUART0_TX/ADC_IN11_4") (pintype "passive"))
    )
    (net (code "59") (name "/UART1_RXD") (class "Default")
      (node (ref "R31") (pin "1") (pinfunction "1_1") (pintype "passive"))
      (node (ref "U2") (pin "34") (pinfunction "PB13/SEG11/UART1_RX/LPUART1_RX_34") (pintype "passive"))
    )
    (net (code "60") (name "/UART1_TXD") (class "Default")
      (node (ref "R30") (pin "1") (pinfunction "1_1") (pintype "passive"))
      (node (ref "U2") (pin "35") (pinfunction "PB14/SEG12/UART1_TX/LPUART1_TX_35") (pintype "passive"))
    )
    (net (code "61") (name "/UART3_RXD") (class "Default")
      (node (ref "R61") (pin "1") (pinfunction "1_1") (pintype "passive"))
      (node (ref "U2") (pin "21") (pinfunction "PB0/SEG34/UART3_RX/SPI1_MISO/OPA1_OUT3_21") (pintype "passive"))
    )
    (net (code "62") (name "/UART3_TXD") (class "Default")
      (node (ref "R62") (pin "1") (pinfunction "1_1") (pintype "passive"))
      (node (ref "U2") (pin "22") (pinfunction "PB1/SEG35/UART3_TX/SPI1_MOSI/OPA1_OUT4_22") (pintype "passive"))
    )
    (net (code "63") (name "/UART4_RXD") (class "Default")
      (node (ref "R65") (pin "1") (pinfunction "1_1") (pintype "passive"))
      (node (ref "U2") (pin "6") (pinfunction "PA0/COM0/UART4_RX/ADC_IN5/LUT3_OUT_6") (pintype "passive"))
    )
    (net (code "64") (name "/UART4_TXD") (class "Default")
      (node (ref "R66") (pin "1") (pinfunction "1_1") (pintype "passive"))
      (node (ref "U2") (pin "7") (pinfunction "PA1/COM1/UART4_TX/ADC_IN12/LUT2_OUT_7") (pintype "passive"))
    )
    (net (code "65") (name "/UMU_RXD") (class "Default")
      (node (ref "J2") (pin "19") (pinfunction "19_19") (pintype "passive"))
      (node (ref "R66") (pin "2") (pinfunction "2_2") (pintype "passive"))
    )
    (net (code "66") (name "/UMU_TXD") (class "Default")
      (node (ref "J2") (pin "17") (pinfunction "17_17") (pintype "passive"))
      (node (ref "R65") (pin "2") (pinfunction "2_2") (pintype "passive"))
    )
    (net (code "67") (name "/UMU_WAKE") (class "Default")
      (node (ref "J2") (pin "14") (pinfunction "14_14") (pintype "passive"))
      (node (ref "R56") (pin "2") (pinfunction "2_2") (pintype "passive"))
      (node (ref "U2") (pin "23") (pinfunction "PB2(WKUP2)/VCIN1/UART4_RX/ATIM_CHIN_23") (pintype "passive"))
    )
    (net (code "68") (name "/Vout_3V6") (class "Default")
      (node (ref "Q12") (pin "2") (pinfunction "S_2") (pintype "passive"))
      (node (ref "R60") (pin "1") (pinfunction "1_1") (pintype "passive"))
      (node (ref "R63") (pin "2") (pinfunction "2_2") (pintype "passive"))
      (node (ref "R64") (pin "1") (pinfunction "1_1") (pintype "passive"))
    )
    (net (code "69") (name "/Vout_3V6_1") (class "Default")
      (node (ref "D2") (pin "2") (pinfunction "2_2") (pintype "passive"))
      (node (ref "J3") (pin "16") (pinfunction "16_16") (pintype "passive"))
    )
    (net (code "70") (name "/Vout_3V6_CHK") (class "Default")
      (node (ref "U2") (pin "72") (pinfunction "PD1/SEG23/UART5_TX/ADC_IN1/GPT2_CH2_72") (pintype "passive"))
    )
    (net (code "71") (name "/Vout_3V6_CTL") (class "Default")
      (node (ref "U2") (pin "30") (pinfunction "PB9/SEG8/SPI0_SCK/GPT0_ETR/COMP1_INP2_30") (pintype "passive"))
    )
    (net (code "72") (name "/Vout_7V2") (class "Default")
      (node (ref "Q10") (pin "2") (pinfunction "S_2") (pintype "passive"))
      (node (ref "R33") (pin "1") (pinfunction "1_1") (pintype "passive"))
      (node (ref "R34") (pin "2") (pinfunction "2_2") (pintype "passive"))
      (node (ref "R35") (pin "1") (pinfunction "1_1") (pintype "passive"))
    )
    (net (code "73") (name "/Vout_7V2_1") (class "Default")
      (node (ref "D1") (pin "2") (pinfunction "2_2") (pintype "passive"))
      (node (ref "J2") (pin "1") (pinfunction "1_1") (pintype "passive"))
    )
    (net (code "74") (name "/Vout_7V2_CHK") (class "Default")
      (node (ref "U2") (pin "71") (pinfunction "PD0/SEG22/UART5_RX/ADC_IN7/GPT2_CH1_71") (pintype "passive"))
    )
    (net (code "75") (name "/Vout_7V2_CTL") (class "Default")
      (node (ref "U2") (pin "31") (pinfunction "PB10/SEG9/SPI0_MISO/GPT0_CH1/OPA1_INN1_31") (pintype "passive"))
    )
    (net (code "76") (name "/XT1") (class "Default")
      (node (ref "C5") (pin "1") (pinfunction "1_1") (pintype "passive"))
      (node (ref "U2") (pin "61") (pinfunction "XT32KI_61") (pintype "passive"))
      (node (ref "Y1") (pin "1") (pinfunction "1_1") (pintype "passive"))
    )
    (net (code "77") (name "/XT2") (class "Default")
      (node (ref "C6") (pin "2") (pinfunction "2_2") (pintype "passive"))
      (node (ref "U2") (pin "60") (pinfunction "XT32KO_60") (pintype "passive"))
      (node (ref "Y1") (pin "2") (pinfunction "2_2") (pintype "passive"))
    )
    (net (code "78") (name "/gongwei1") (class "Default")
      (node (ref "P2") (pin "1") (pinfunction "1_1") (pintype "passive"))
      (node (ref "U2") (pin "29") (pinfunction "PB8/SEG7/SPI0_SSN/ATIM_CH3N/COMP1_INP1_29") (pintype "passive"))
    )
    (net (code "79") (name "/gongwei2") (class "Default")
      (node (ref "P2") (pin "3") (pinfunction "3_3") (pintype "passive"))
      (node (ref "U2") (pin "28") (pinfunction "PB7/SEG6/ATIM_CH4/SPI2_SCK/ANATST_28") (pintype "passive"))
    )
    (net (code "80") (name "/gongwei3") (class "Default")
      (node (ref "P2") (pin "5") (pinfunction "5_5") (pintype "passive"))
      (node (ref "U2") (pin "27") (pinfunction "PB6/SEG5/ATIM_CH3/SPI2_SSN_27") (pintype "passive"))
    )
    (net (code "81") (name "/gongwei4") (class "Default")
      (node (ref "P2") (pin "7") (pinfunction "7_7") (pintype "passive"))
      (node (ref "U2") (pin "26") (pinfunction "PB5/SEG4/ATIM_CH2/LPUART2_TX/COMP3_INN2_26") (pintype "passive"))
    )
    (net (code "82") (name "3.3V") (class "Default")
      (node (ref "C10") (pin "2") (pinfunction "2_2") (pintype "passive"))
      (node (ref "C2") (pin "2") (pinfunction "2_2") (pintype "passive"))
      (node (ref "C7") (pin "2") (pinfunction "2_2") (pintype "passive"))
      (node (ref "D3") (pin "1") (pinfunction "1_1") (pintype "passive"))
      (node (ref "J1") (pin "5") (pinfunction "5_5") (pintype "passive"))
      (node (ref "P1") (pin "1") (pinfunction "1_1") (pintype "passive"))
      (node (ref "P1") (pin "4") (pinfunction "4_4") (pintype "passive"))
      (node (ref "R10") (pin "1") (pinfunction "1_1") (pintype "passive"))
      (node (ref "R18") (pin "2") (pinfunction "2_2") (pintype "passive"))
      (node (ref "R22") (pin "1") (pinfunction "1_1") (pintype "passive"))
      (node (ref "R23") (pin "1") (pinfunction "1_1") (pintype "passive"))
      (node (ref "R37") (pin "1") (pinfunction "1_1") (pintype "passive"))
      (node (ref "R42") (pin "1") (pinfunction "1_1") (pintype "passive"))
      (node (ref "R43") (pin "1") (pinfunction "1_1") (pintype "passive"))
      (node (ref "R46") (pin "1") (pinfunction "1_1") (pintype "passive"))
      (node (ref "R88") (pin "1") (pinfunction "1_1") (pintype "passive"))
      (node (ref "U1") (pin "5") (pinfunction "Vs_5") (pintype "passive"))
      (node (ref "U2") (pin "64") (pinfunction "VDD(VDDA)_64") (pintype "passive"))
      (node (ref "U2") (pin "66") (pinfunction "VREFP_66") (pintype "passive"))
      (node (ref "U3") (pin "5") (pinfunction "Vs_5") (pintype "passive"))
    )
    (net (code "83") (name "12V_Out1") (class "Default")
      (node (ref "J3") (pin "17") (pinfunction "17_17") (pintype "passive"))
      (node (ref "J3") (pin "19") (pinfunction "19_19") (pintype "passive"))
    )
    (net (code "84") (name "12V_Out2") (class "Default")
      (node (ref "J3") (pin "18") (pinfunction "18_18") (pintype "passive"))
      (node (ref "J3") (pin "20") (pinfunction "20_20") (pintype "passive"))
    )
    (net (code "85") (name "GND") (class "Default")
      (node (ref "C1") (pin "2") (pinfunction "2_2") (pintype "passive"))
      (node (ref "C10") (pin "1") (pinfunction "1_1") (pintype "passive"))
      (node (ref "C2") (pin "1") (pinfunction "1_1") (pintype "passive"))
      (node (ref "C3") (pin "2") (pinfunction "2_2") (pintype "passive"))
      (node (ref "C5") (pin "2") (pinfunction "2_2") (pintype "passive"))
      (node (ref "C6") (pin "1") (pinfunction "1_1") (pintype "passive"))
      (node (ref "C7") (pin "1") (pinfunction "1_1") (pintype "passive"))
      (node (ref "C8") (pin "2") (pinfunction "2_2") (pintype "passive"))
      (node (ref "J1") (pin "4") (pinfunction "4_4") (pintype "passive"))
      (node (ref "J2") (pin "2") (pinfunction "2_2") (pintype "passive"))
      (node (ref "J3") (pin "1") (pinfunction "1_1") (pintype "passive"))
      (node (ref "J3") (pin "3") (pinfunction "3_3") (pintype "passive"))
      (node (ref "P2") (pin "2") (pinfunction "2_2") (pintype "passive"))
      (node (ref "P2") (pin "4") (pinfunction "4_4") (pintype "passive"))
      (node (ref "P2") (pin "6") (pinfunction "6_6") (pintype "passive"))
      (node (ref "P2") (pin "8") (pinfunction "8_8") (pintype "passive"))
      (node (ref "P3") (pin "3") (pinfunction "3_3") (pintype "passive"))
      (node (ref "P4") (pin "1") (pinfunction "1_1") (pintype "passive"))
      (node (ref "P5") (pin "1") (pinfunction "1_1") (pintype "passive"))
      (node (ref "P6") (pin "1") (pinfunction "1_1") (pintype "passive"))
      (node (ref "P7") (pin "5") (pinfunction "GND_5") (pintype "passive"))
      (node (ref "Q11") (pin "2") (pinfunction "E_2") (pintype "passive"))
      (node (ref "Q21") (pin "2") (pinfunction "E_2") (pintype "passive"))
      (node (ref "Q4") (pin "2") (pinfunction "E_2") (pintype "passive"))
      (node (ref "Q5") (pin "2") (pinfunction "E_2") (pintype "passive"))
      (node (ref "Q6") (pin "2") (pinfunction "E_2") (pintype "passive"))
      (node (ref "Q7") (pin "3") (pinfunction "C_3") (pintype "passive"))
      (node (ref "Q8") (pin "2") (pinfunction "E_2") (pintype "passive"))
      (node (ref "Q9") (pin "2") (pinfunction "E_2") (pintype "passive"))
      (node (ref "R11") (pin "2") (pinfunction "2_2") (pintype "passive"))
      (node (ref "R12") (pin "2") (pinfunction "2_2") (pintype "passive"))
      (node (ref "R13") (pin "2") (pinfunction "2_2") (pintype "passive"))
      (node (ref "R25") (pin "1") (pinfunction "1_1") (pintype "passive"))
      (node (ref "R26") (pin "1") (pinfunction "1_1") (pintype "passive"))
      (node (ref "R29") (pin "1") (pinfunction "1_1") (pintype "passive"))
      (node (ref "R56") (pin "1") (pinfunction "1_1") (pintype "passive"))
      (node (ref "R89") (pin "1") (pinfunction "1_1") (pintype "passive"))
      (node (ref "R97") (pin "2") (pinfunction "2_2") (pintype "passive"))
      (node (ref "U1") (pin "1") (pinfunction "A1_1") (pintype "passive"))
      (node (ref "U1") (pin "2") (pinfunction "A0_2") (pintype "passive"))
      (node (ref "U1") (pin "6") (pinfunction "GND_6") (pintype "passive"))
      (node (ref "U2") (pin "63") (pinfunction "VSS(VSSA)_63") (pintype "passive"))
      (node (ref "U2") (pin "65") (pinfunction "VREFN_65") (pintype "passive"))
      (node (ref "U3") (pin "1") (pinfunction "A1_1") (pintype "passive"))
      (node (ref "U3") (pin "2") (pinfunction "A0_2") (pintype "passive"))
      (node (ref "U3") (pin "6") (pinfunction "GND_6") (pintype "passive"))
    )
    (net (code "86") (name "Net-(D3-Pad2)") (class "Default")
      (node (ref "D3") (pin "2") (pinfunction "2_2") (pintype "passive"))
      (node (ref "R68") (pin "2") (pinfunction "2_2") (pintype "passive"))
    )
    (net (code "87") (name "Net-(J1-Pad1)") (class "Default")
      (node (ref "J1") (pin "1") (pinfunction "1_1") (pintype "passive"))
      (node (ref "R36") (pin "2") (pinfunction "2_2") (pintype "passive"))
    )
    (net (code "88") (name "Net-(J3-Pad2)") (class "Default")
      (node (ref "J3") (pin "2") (pinfunction "2_2") (pintype "passive"))
      (node (ref "R38") (pin "1") (pinfunction "1_1") (pintype "passive"))
    )
    (net (code "89") (name "Net-(J3-Pad4)") (class "Default")
      (node (ref "J3") (pin "4") (pinfunction "4_4") (pintype "passive"))
      (node (ref "R39") (pin "1") (pinfunction "1_1") (pintype "passive"))
    )
    (net (code "90") (name "Net-(J3-Pad5)") (class "Default")
      (node (ref "J3") (pin "5") (pinfunction "5_5") (pintype "passive"))
      (node (ref "R58") (pin "2") (pinfunction "2_2") (pintype "passive"))
    )
    (net (code "91") (name "Net-(J3-Pad6)") (class "Default")
      (node (ref "J3") (pin "6") (pinfunction "6_6") (pintype "passive"))
      (node (ref "R41") (pin "1") (pinfunction "1_1") (pintype "passive"))
    )
    (net (code "92") (name "Net-(J3-Pad7)") (class "Default")
      (node (ref "J3") (pin "7") (pinfunction "7_7") (pintype "passive"))
      (node (ref "R40") (pin "2") (pinfunction "2_2") (pintype "passive"))
    )
    (net (code "93") (name "Net-(J3-Pad8)") (class "Default")
      (node (ref "J3") (pin "8") (pinfunction "8_8") (pintype "passive"))
      (node (ref "R45") (pin "1") (pinfunction "1_1") (pintype "passive"))
    )
    (net (code "94") (name "Net-(J3-Pad9)") (class "Default")
      (node (ref "J3") (pin "9") (pinfunction "9_9") (pintype "passive"))
      (node (ref "R44") (pin "2") (pinfunction "2_2") (pintype "passive"))
    )
    (net (code "95") (name "Net-(J3-Pad10)") (class "Default")
      (node (ref "J3") (pin "10") (pinfunction "10_10") (pintype "passive"))
      (node (ref "R48") (pin "1") (pinfunction "1_1") (pintype "passive"))
    )
    (net (code "96") (name "Net-(J3-Pad11)") (class "Default")
      (node (ref "J3") (pin "11") (pinfunction "11_11") (pintype "passive"))
      (node (ref "R47") (pin "2") (pinfunction "2_2") (pintype "passive"))
    )
    (net (code "97") (name "Net-(J3-Pad12)") (class "Default")
      (node (ref "J3") (pin "12") (pinfunction "12_12") (pintype "passive"))
      (node (ref "R50") (pin "1") (pinfunction "1_1") (pintype "passive"))
    )
    (net (code "98") (name "Net-(J3-Pad13)") (class "Default")
      (node (ref "J3") (pin "13") (pinfunction "13_13") (pintype "passive"))
      (node (ref "R49") (pin "2") (pinfunction "2_2") (pintype "passive"))
    )
    (net (code "99") (name "Net-(J3-Pad14)") (class "Default")
      (node (ref "J3") (pin "14") (pinfunction "14_14") (pintype "passive"))
      (node (ref "R52") (pin "1") (pinfunction "1_1") (pintype "passive"))
    )
    (net (code "100") (name "Net-(J3-Pad15)") (class "Default")
      (node (ref "J3") (pin "15") (pinfunction "15_15") (pintype "passive"))
      (node (ref "R51") (pin "2") (pinfunction "2_2") (pintype "passive"))
    )
    (net (code "101") (name "Net-(P1-Pad2)") (class "Default")
      (node (ref "P1") (pin "2") (pinfunction "2_2") (pintype "passive"))
      (node (ref "R17") (pin "2") (pinfunction "2_2") (pintype "passive"))
    )
    (net (code "102") (name "Net-(P1-Pad3)") (class "Default")
      (node (ref "P1") (pin "3") (pinfunction "3_3") (pintype "passive"))
      (node (ref "R24") (pin "2") (pinfunction "2_2") (pintype "passive"))
    )
    (net (code "103") (name "Net-(P4-Pad2)") (class "Default")
      (node (ref "P4") (pin "2") (pinfunction "2_2") (pintype "passive"))
      (node (ref "R69") (pin "1") (pinfunction "1_1") (pintype "passive"))
    )
    (net (code "104") (name "Net-(P4-Pad3)") (class "Default")
      (node (ref "P4") (pin "3") (pinfunction "3_3") (pintype "passive"))
      (node (ref "R67") (pin "1") (pinfunction "1_1") (pintype "passive"))
    )
    (net (code "105") (name "Net-(Q1-B)") (class "Default")
      (node (ref "Q1") (pin "1") (pinfunction "B_1") (pintype "passive"))
      (node (ref "R1") (pin "1") (pinfunction "1_1") (pintype "passive"))
      (node (ref "R7") (pin "1") (pinfunction "1_1") (pintype "passive"))
    )
    (net (code "106") (name "Net-(Q1-C)") (class "Default")
      (node (ref "Q1") (pin "3") (pinfunction "C_3") (pintype "passive"))
      (node (ref "R3") (pin "1") (pinfunction "1_1") (pintype "passive"))
    )
    (net (code "107") (name "Net-(Q2-B)") (class "Default")
      (node (ref "Q2") (pin "1") (pinfunction "B_1") (pintype "passive"))
      (node (ref "R2") (pin "1") (pinfunction "1_1") (pintype "passive"))
      (node (ref "R8") (pin "1") (pinfunction "1_1") (pintype "passive"))
    )
    (net (code "108") (name "Net-(Q2-C)") (class "Default")
      (node (ref "Q2") (pin "3") (pinfunction "C_3") (pintype "passive"))
      (node (ref "R4") (pin "1") (pinfunction "1_1") (pintype "passive"))
    )
    (net (code "109") (name "Net-(Q3-B)") (class "Default")
      (node (ref "Q3") (pin "1") (pinfunction "B_1") (pintype "passive"))
      (node (ref "R5") (pin "1") (pinfunction "1_1") (pintype "passive"))
      (node (ref "R9") (pin "1") (pinfunction "1_1") (pintype "passive"))
    )
    (net (code "110") (name "Net-(Q3-C)") (class "Default")
      (node (ref "Q3") (pin "3") (pinfunction "C_3") (pintype "passive"))
      (node (ref "R6") (pin "1") (pinfunction "1_1") (pintype "passive"))
    )
    (net (code "111") (name "Net-(Q4-B)") (class "Default")
      (node (ref "Q4") (pin "1") (pinfunction "B_1") (pintype "passive"))
      (node (ref "R14") (pin "2") (pinfunction "2_2") (pintype "passive"))
    )
    (net (code "112") (name "Net-(Q4-C)") (class "Default")
      (node (ref "Q4") (pin "3") (pinfunction "C_3") (pintype "passive"))
      (node (ref "R7") (pin "2") (pinfunction "2_2") (pintype "passive"))
    )
    (net (code "113") (name "Net-(Q5-B)") (class "Default")
      (node (ref "Q5") (pin "1") (pinfunction "B_1") (pintype "passive"))
      (node (ref "R15") (pin "2") (pinfunction "2_2") (pintype "passive"))
    )
    (net (code "114") (name "Net-(Q5-C)") (class "Default")
      (node (ref "Q5") (pin "3") (pinfunction "C_3") (pintype "passive"))
      (node (ref "R8") (pin "2") (pinfunction "2_2") (pintype "passive"))
    )
    (net (code "115") (name "Net-(Q6-B)") (class "Default")
      (node (ref "Q6") (pin "1") (pinfunction "B_1") (pintype "passive"))
      (node (ref "R16") (pin "2") (pinfunction "2_2") (pintype "passive"))
    )
    (net (code "116") (name "Net-(Q6-C)") (class "Default")
      (node (ref "Q6") (pin "3") (pinfunction "C_3") (pintype "passive"))
      (node (ref "R9") (pin "2") (pinfunction "2_2") (pintype "passive"))
    )
    (net (code "117") (name "Net-(Q7-B)") (class "Default")
      (node (ref "Q7") (pin "1") (pinfunction "B_1") (pintype "passive"))
      (node (ref "R19") (pin "2") (pinfunction "2_2") (pintype "passive"))
    )
    (net (code "118") (name "Net-(Q7-E)") (class "Default")
      (node (ref "Q7") (pin "2") (pinfunction "E_2") (pintype "passive"))
      (node (ref "R17") (pin "1") (pinfunction "1_1") (pintype "passive"))
    )
    (net (code "119") (name "Net-(Q8-B)") (class "Default")
      (node (ref "C3") (pin "1") (pinfunction "1_1") (pintype "passive"))
      (node (ref "Q8") (pin "1") (pinfunction "B_1") (pintype "passive"))
      (node (ref "R24") (pin "1") (pinfunction "1_1") (pintype "passive"))
      (node (ref "R29") (pin "2") (pinfunction "2_2") (pintype "passive"))
    )
    (net (code "120") (name "Net-(Q9-B)") (class "Default")
      (node (ref "Q9") (pin "1") (pinfunction "B_1") (pintype "passive"))
      (node (ref "R32") (pin "1") (pinfunction "1_1") (pintype "passive"))
    )
    (net (code "121") (name "Net-(Q9-C)") (class "Default")
      (node (ref "Q9") (pin "3") (pinfunction "C_3") (pintype "passive"))
      (node (ref "R28") (pin "2") (pinfunction "2_2") (pintype "passive"))
    )
    (net (code "122") (name "Net-(Q10-D)") (class "Default")
      (node (ref "D1") (pin "1") (pinfunction "1_1") (pintype "passive"))
      (node (ref "Q10") (pin "3") (pinfunction "D_3") (pintype "passive"))
      (node (ref "R27") (pin "1") (pinfunction "1_1") (pintype "passive"))
      (node (ref "R33") (pin "2") (pinfunction "2_2") (pintype "passive"))
    )
    (net (code "123") (name "Net-(Q10-G)") (class "Default")
      (node (ref "Q10") (pin "1") (pinfunction "G_1") (pintype "passive"))
      (node (ref "R28") (pin "1") (pinfunction "1_1") (pintype "passive"))
      (node (ref "R34") (pin "1") (pinfunction "1_1") (pintype "passive"))
    )
    (net (code "124") (name "Net-(Q11-B)") (class "Default")
      (node (ref "Q11") (pin "1") (pinfunction "B_1") (pintype "passive"))
      (node (ref "R59") (pin "1") (pinfunction "1_1") (pintype "passive"))
    )
    (net (code "125") (name "Net-(Q11-C)") (class "Default")
      (node (ref "Q11") (pin "3") (pinfunction "C_3") (pintype "passive"))
      (node (ref "R55") (pin "2") (pinfunction "2_2") (pintype "passive"))
    )
    (net (code "126") (name "Net-(Q12-D)") (class "Default")
      (node (ref "D2") (pin "1") (pinfunction "1_1") (pintype "passive"))
      (node (ref "Q12") (pin "3") (pinfunction "D_3") (pintype "passive"))
      (node (ref "R54") (pin "1") (pinfunction "1_1") (pintype "passive"))
      (node (ref "R60") (pin "2") (pinfunction "2_2") (pintype "passive"))
    )
    (net (code "127") (name "Net-(Q12-G)") (class "Default")
      (node (ref "Q12") (pin "1") (pinfunction "G_1") (pintype "passive"))
      (node (ref "R55") (pin "1") (pinfunction "1_1") (pintype "passive"))
      (node (ref "R63") (pin "1") (pinfunction "1_1") (pintype "passive"))
    )
    (net (code "128") (name "Net-(Q20-B)") (class "Default")
      (node (ref "Q20") (pin "1") (pinfunction "B_1") (pintype "passive"))
      (node (ref "R94") (pin "1") (pinfunction "1_1") (pintype "passive"))
      (node (ref "R96") (pin "1") (pinfunction "1_1") (pintype "passive"))
    )
    (net (code "129") (name "Net-(Q20-C)") (class "Default")
      (node (ref "Q20") (pin "3") (pinfunction "C_3") (pintype "passive"))
      (node (ref "R95") (pin "1") (pinfunction "1_1") (pintype "passive"))
    )
    (net (code "130") (name "Net-(Q21-B)") (class "Default")
      (node (ref "Q21") (pin "1") (pinfunction "B_1") (pintype "passive"))
      (node (ref "R98") (pin "2") (pinfunction "2_2") (pintype "passive"))
    )
    (net (code "131") (name "Net-(Q21-C)") (class "Default")
      (node (ref "Q21") (pin "3") (pinfunction "C_3") (pintype "passive"))
      (node (ref "R96") (pin "2") (pinfunction "2_2") (pintype "passive"))
    )
    (net (code "132") (name "Net-(U1-Vin+)") (class "Default")
      (node (ref "C4") (pin "2") (pinfunction "2_2") (pintype "passive"))
      (node (ref "R35") (pin "2") (pinfunction "2_2") (pintype "passive"))
      (node (ref "U1") (pin "8") (pinfunction "Vin+_8") (pintype "passive"))
    )
    (net (code "133") (name "Net-(U1-Vin-)") (class "Default")
      (node (ref "C4") (pin "1") (pinfunction "1_1") (pintype "passive"))
      (node (ref "R27") (pin "2") (pinfunction "2_2") (pintype "passive"))
      (node (ref "U1") (pin "7") (pinfunction "Vin-_7") (pintype "passive"))
    )
    (net (code "134") (name "Net-(U2-VDD15)") (class "Default")
      (node (ref "C8") (pin "1") (pinfunction "1_1") (pintype "passive"))
      (node (ref "U2") (pin "62") (pinfunction "VDD15_62") (pintype "passive"))
    )
    (net (code "135") (name "Net-(U3-Vin+)") (class "Default")
      (node (ref "C9") (pin "2") (pinfunction "2_2") (pintype "passive"))
      (node (ref "R64") (pin "2") (pinfunction "2_2") (pintype "passive"))
      (node (ref "U3") (pin "8") (pinfunction "Vin+_8") (pintype "passive"))
    )
    (net (code "136") (name "Net-(U3-Vin-)") (class "Default")
      (node (ref "C9") (pin "1") (pinfunction "1_1") (pintype "passive"))
      (node (ref "R54") (pin "2") (pinfunction "2_2") (pintype "passive"))
      (node (ref "U3") (pin "7") (pinfunction "Vin-_7") (pintype "passive"))
    )
    (net (code "137") (name "VIN_5V") (class "Default")
      (node (ref "P3") (pin "2") (pinfunction "2_2") (pintype "passive"))
    )
    (net (code "138") (name "unconnected-(P4-Pad4)") (class "Default")
      (node (ref "P4") (pin "4") (pinfunction "4_4") (pintype "passive+no_connect"))
    )
    (net (code "139") (name "unconnected-(P5-Pad4)") (class "Default")
      (node (ref "P5") (pin "4") (pinfunction "4_4") (pintype "passive+no_connect"))
    )
    (net (code "140") (name "unconnected-(U2-PA5{slash}COM5{slash}SEG29{slash}GPT1_CH4{slash}COMP2_INN2-Pad11)") (class "Default")
      (node (ref "U2") (pin "11") (pinfunction "PA5/COM5/SEG29/GPT1_CH4/COMP2_INN2_11") (pintype "passive+no_connect"))
    )
    (net (code "141") (name "unconnected-(U2-PA6{slash}COM6{slash}SEG30{slash}OPA1_INN2{slash}CAN_RX-Pad12)") (class "Default")
      (node (ref "U2") (pin "12") (pinfunction "PA6/COM6/SEG30/OPA1_INN2/CAN_RX_12") (pintype "passive+no_connect"))
    )
    (net (code "142") (name "unconnected-(U2-PA7{slash}COM7{slash}SEG31{slash}OPA1_INP2{slash}CAN_TX-Pad13)") (class "Default")
      (node (ref "U2") (pin "13") (pinfunction "PA7/COM7/SEG31/OPA1_INP2/CAN_TX_13") (pintype "passive+no_connect"))
    )
    (net (code "143") (name "unconnected-(U2-PA11{slash}SEG32{slash}SCL0{slash}LPUART2_RX-Pad17)") (class "Default")
      (node (ref "U2") (pin "17") (pinfunction "PA11/SEG32/SCL0/LPUART2_RX_17") (pintype "passive+no_connect"))
    )
    (net (code "144") (name "unconnected-(U2-PA15{slash}WKUP0{slash}SVS{slash}COMP3_OUT-Pad5)") (class "Default")
      (node (ref "U2") (pin "5") (pinfunction "PA15/WKUP0/SVS/COMP3_OUT_5") (pintype "passive+no_connect"))
    )
    (net (code "145") (name "unconnected-(U2-PB3{slash}VCIN2{slash}UART4_TX{slash}ATIM_CH2N-Pad24)") (class "Default")
      (node (ref "U2") (pin "24") (pinfunction "PB3/VCIN2/UART4_TX/ATIM_CH2N_24") (pintype "passive+no_connect"))
    )
    (net (code "146") (name "unconnected-(U2-PC12{slash}SEG21{slash}U7816IO{slash}GPTO_CH4{slash}ADC_IN17-Pad58)") (class "Default")
      (node (ref "U2") (pin "58") (pinfunction "PC12/SEG21/U7816IO/GPTO_CH4/ADC_IN17_58") (pintype "passive+no_connect"))
    )
    (net (code "147") (name "unconnected-(U2-PD9(WKUP8)-Pad19)") (class "Default")
      (node (ref "U2") (pin "19") (pinfunction "PD9(WKUP8)_19") (pintype "passive+no_connect"))
    )
    (net (code "148") (name "unconnected-(U2-PD10{slash}CAN_RX{slash}ADC_IN18-Pad1)") (class "Default")
      (node (ref "U2") (pin "1") (pinfunction "PD10/CAN_RX/ADC_IN18_1") (pintype "passive+no_connect"))
    )
    (net (code "149") (name "unconnected-(U2-PE6(WKUP9)-Pad68)") (class "Default")
      (node (ref "U2") (pin "68") (pinfunction "PE6(WKUP9)_68") (pintype "passive+no_connect"))
    )
    (net (code "150") (name "unconnected-(U2-PE7{slash}COMP3_OUT-Pad69)") (class "Default")
      (node (ref "U2") (pin "69") (pinfunction "PE7/COMP3_OUT_69") (pintype "passive+no_connect"))
    )
    (net (code "151") (name "unconnected-(U2-PE8-Pad20)") (class "Default")
      (node (ref "U2") (pin "20") (pinfunction "PE8_20") (pintype "passive+no_connect"))
    )
    (net (code "152") (name "unconnected-(U2-PE9{slash}CAN_TX{slash}ADC_IN19-Pad2)") (class "Default")
      (node (ref "U2") (pin "2") (pinfunction "PE9/CAN_TX/ADC_IN19_2") (pintype "passive+no_connect"))
    )
    (net (code "153") (name "unconnected-(U2-PH15{slash}RTCOUT{slash}TAMPER-Pad59)") (class "Default")
      (node (ref "U2") (pin "59") (pinfunction "PH15/RTCOUT/TAMPER_59") (pintype "passive+no_connect"))
    )
    (net (code "154") (name "unconnected-(U2-VBAT-Pad67)") (class "Default")
      (node (ref "U2") (pin "67") (pinfunction "VBAT_67") (pintype "passive+no_connect"))
    )
  )
)
